# mcu_stm32f4.net
KiCad netlist of a schematic drawn in Altium Designer
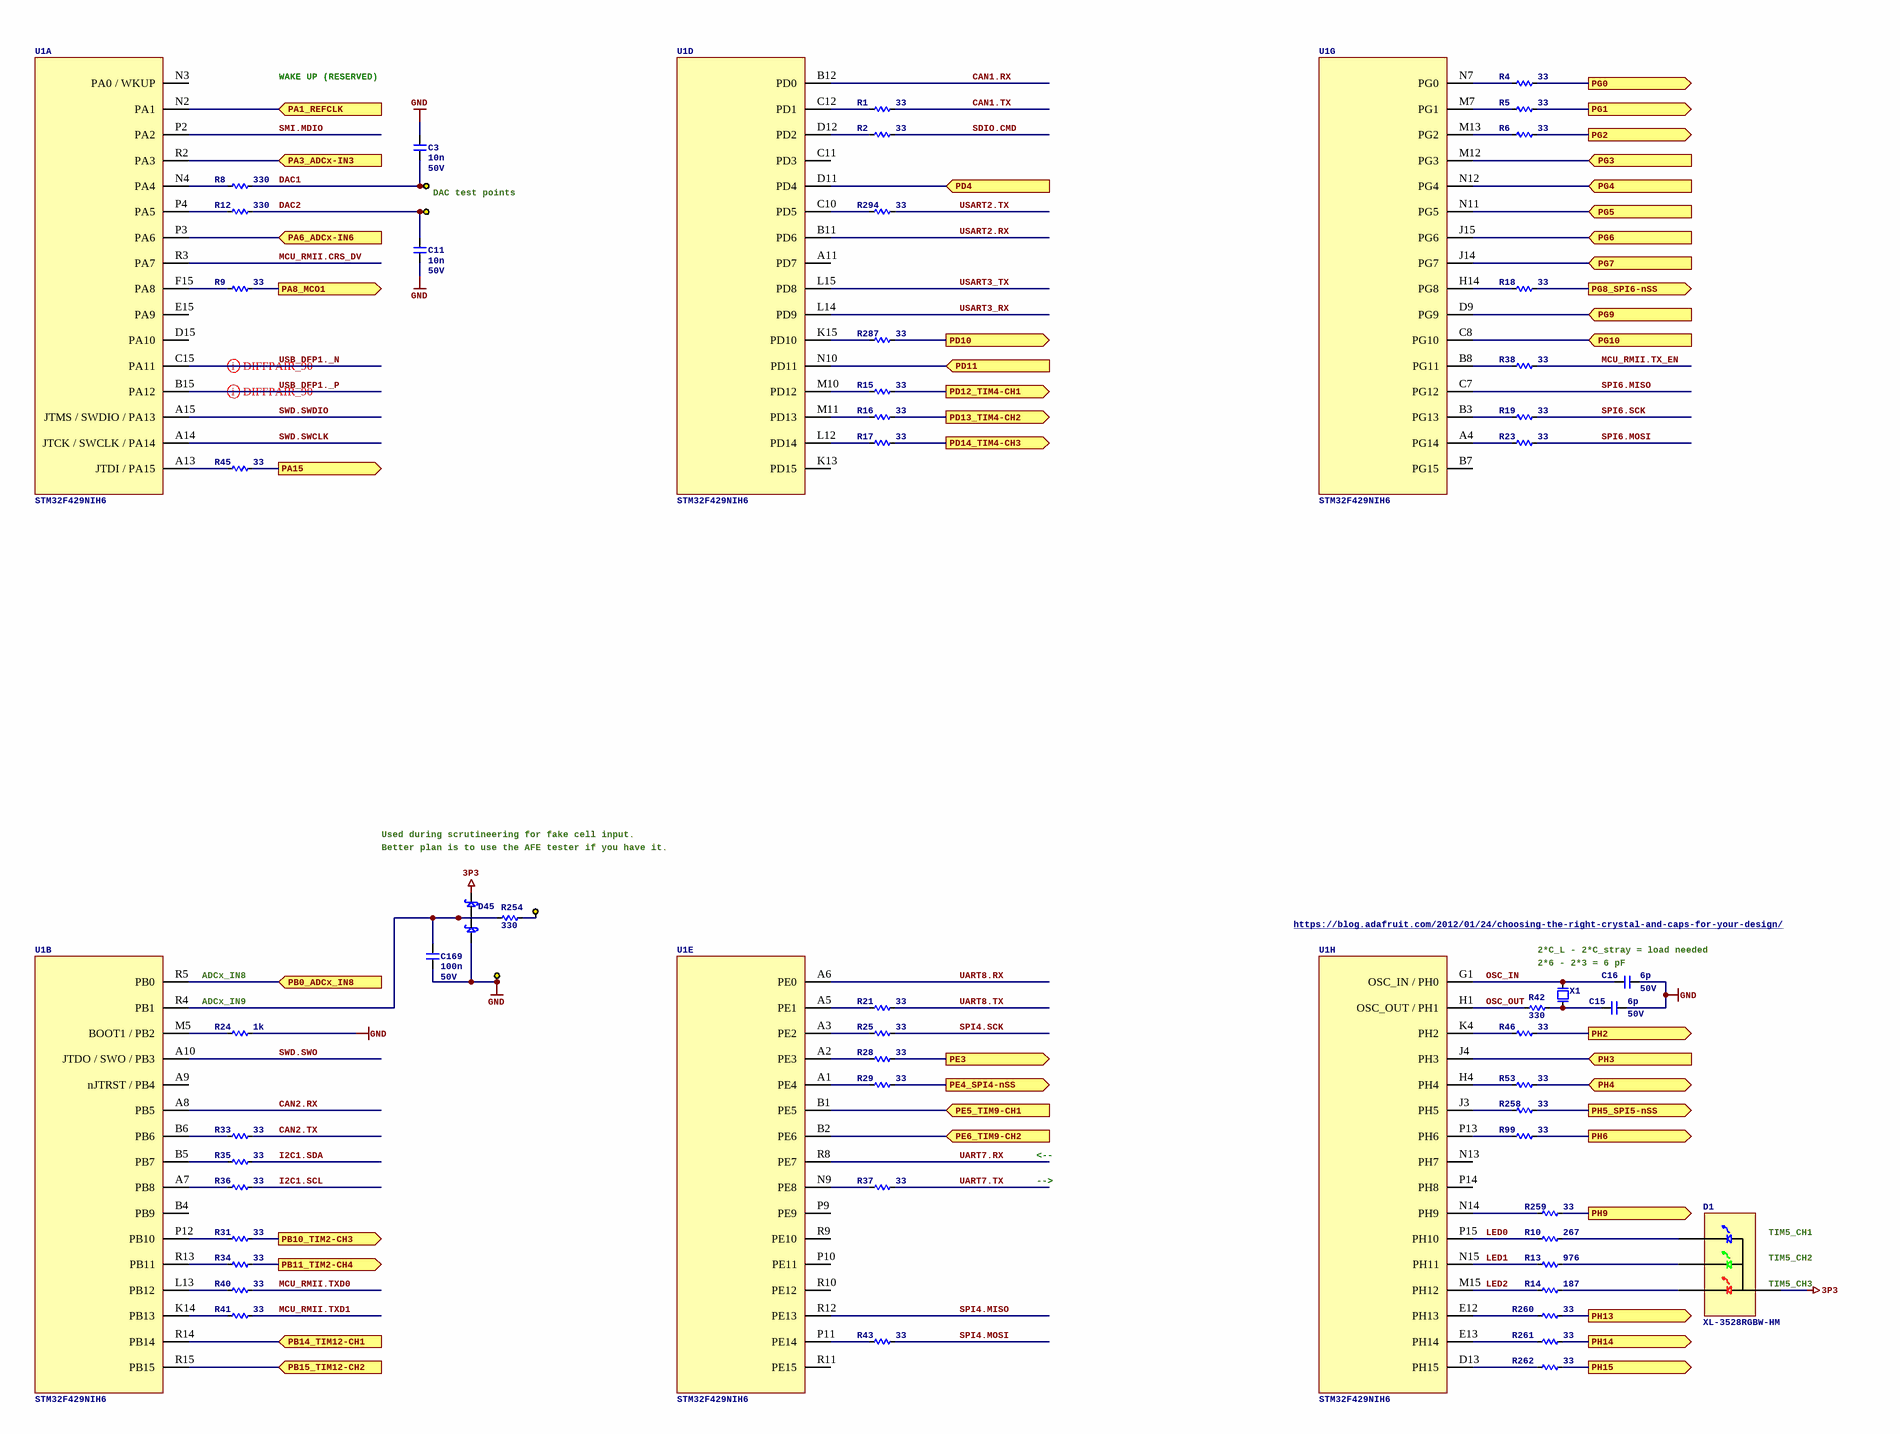
[diagram p0: mcu_stm32f4.SchDoc, top left]
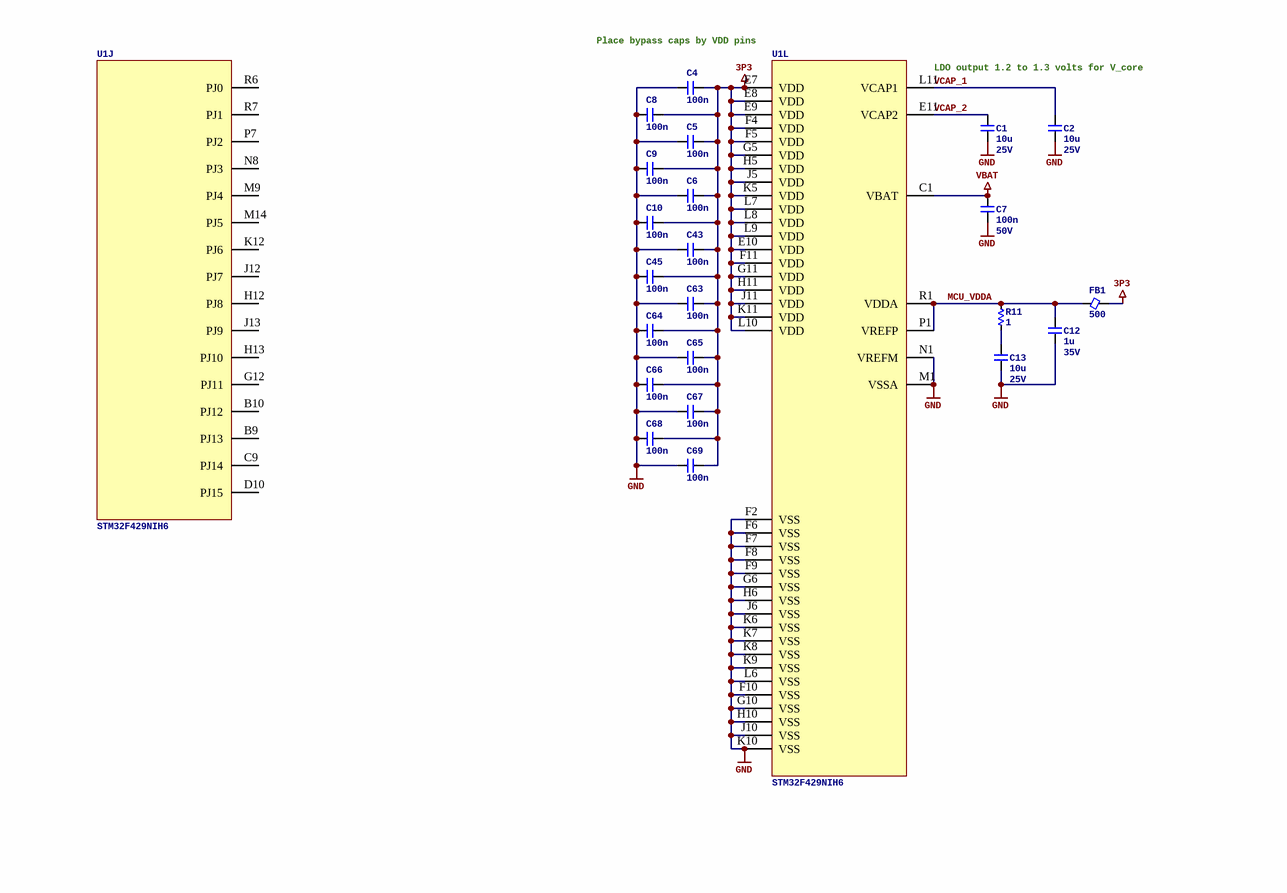
[diagram p1: mcu_stm32f4.SchDoc, top right]
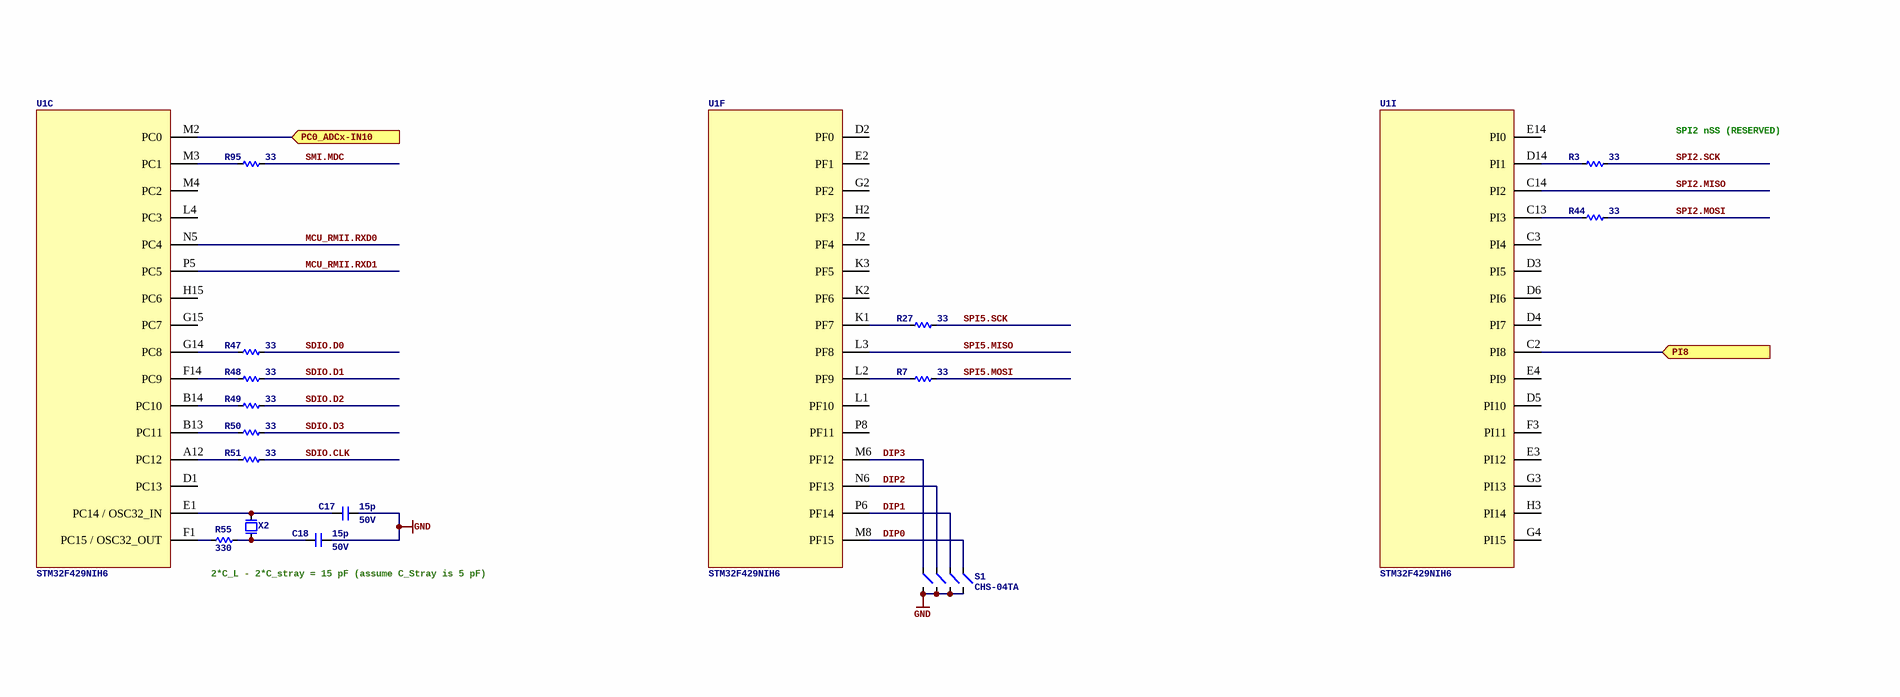
[diagram p2: mcu_stm32f4.SchDoc, bottom left]
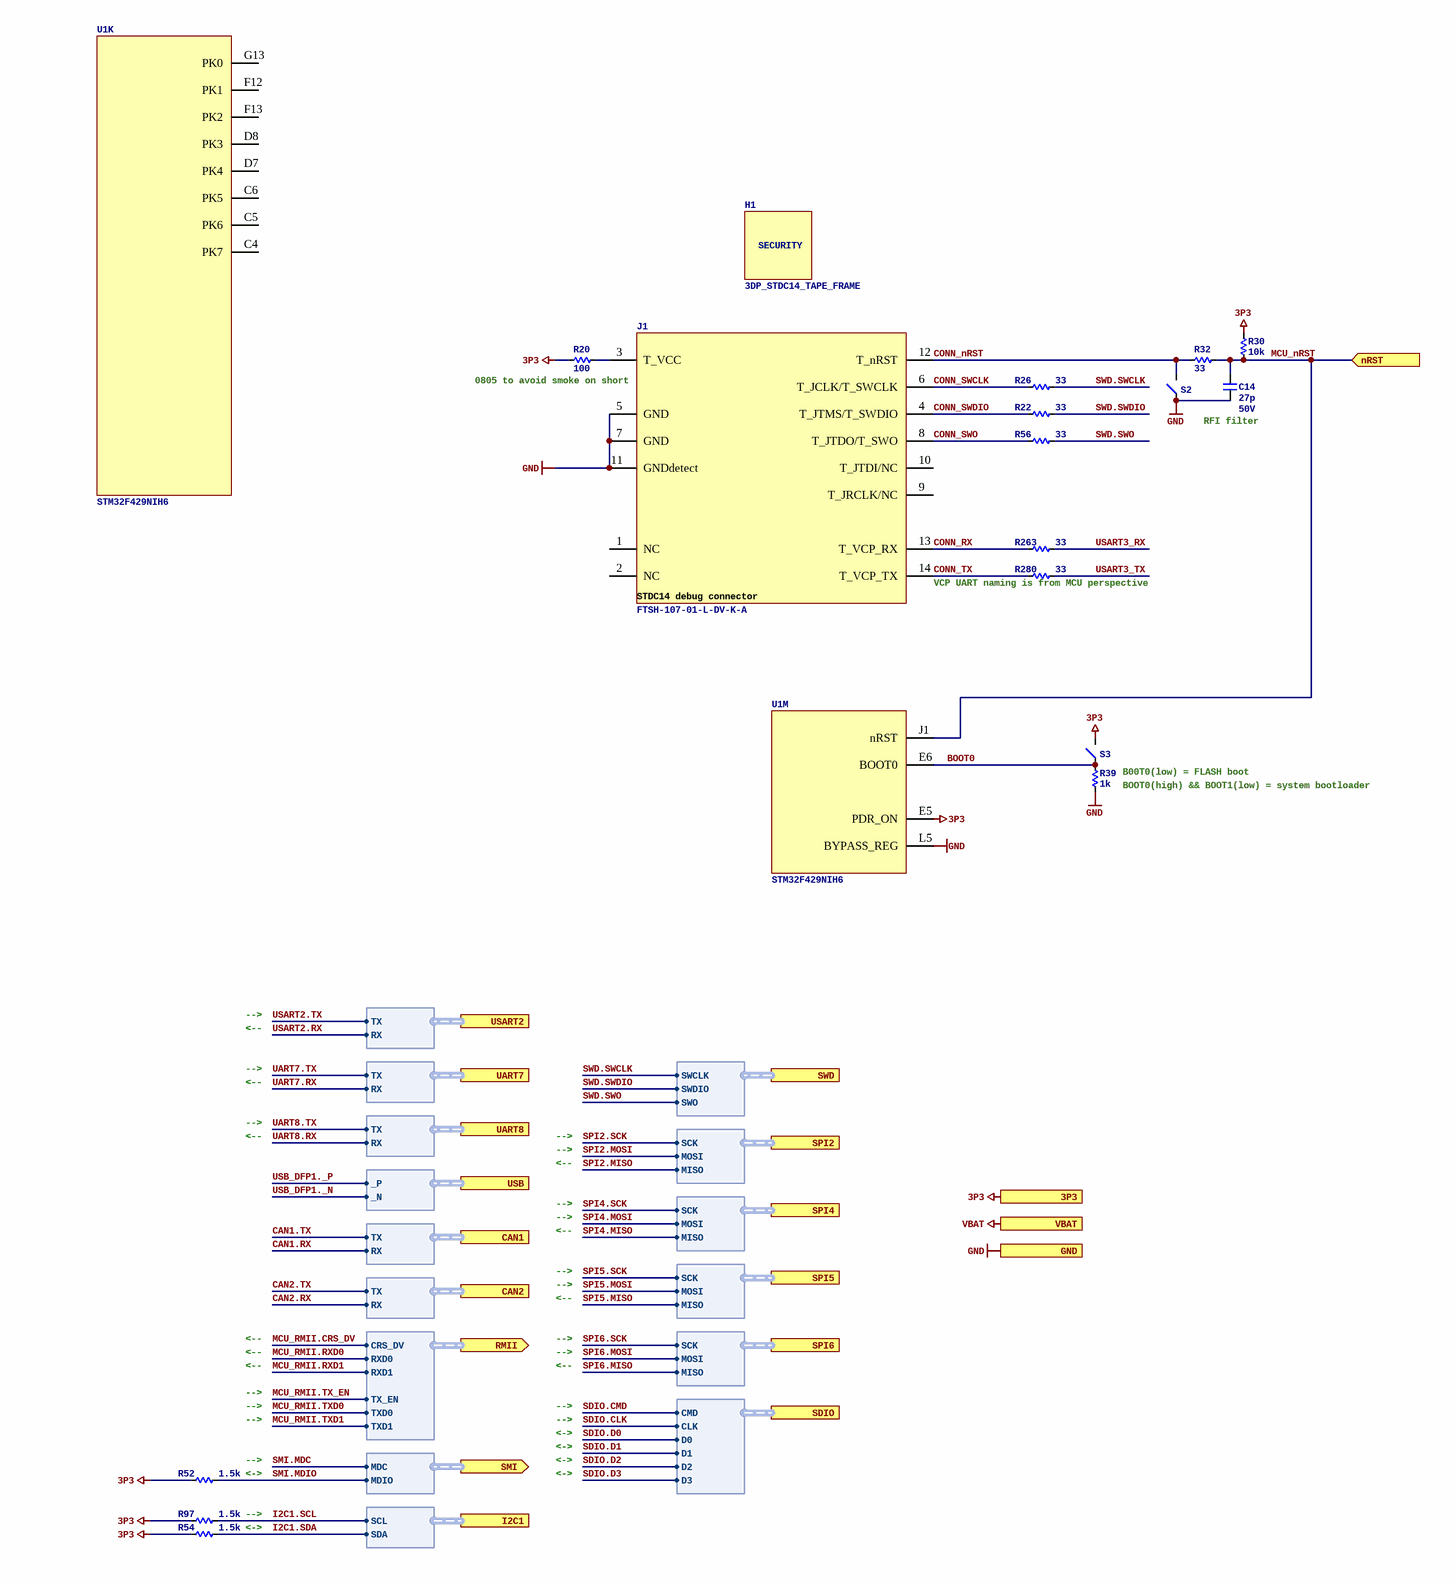
[diagram p3: mcu_stm32f4.SchDoc, bottom right]

(export (version "E")
  (design (tool "Eeschema 10.0.6"))
  (components
    (comp (ref "C1")
      (value "CL10A106MA8NRNC")
      (footprint "C0603")
      (fields
        (field (name "CAPACITANCE") "10u")
        (field (name "MANUFACTURER") "Samsung Electro-Mechanics")
        (field (name "VOLTAGE RATING") "25V")
      )
      (libsource (lib "database") (part "__template_cap"))
    )
    (comp (ref "C2")
      (value "CL10A106MA8NRNC")
      (footprint "C0603")
      (fields
        (field (name "CAPACITANCE") "10u")
        (field (name "MANUFACTURER") "Samsung Electro-Mechanics")
        (field (name "VOLTAGE RATING") "25V")
      )
      (libsource (lib "database") (part "__template_cap"))
    )
    (comp (ref "C3")
      (value "CL05B103KB5NNNC")
      (footprint "C0402")
      (fields
        (field (name "CAPACITANCE") "10n")
        (field (name "MANUFACTURER") "Samsung Electro-Mechanics")
        (field (name "VOLTAGE RATING") "50V")
      )
      (libsource (lib "database") (part "__template_cap"))
    )
    (comp (ref "C4")
      (value "CL05B104KB54PNC")
      (footprint "C0402")
      (fields (field (name "CAPACITANCE") "100n") (field (name "MANUFACTURER") "Samsung Electro-Mechanics"))
      (libsource (lib "database") (part "__template_cap"))
    )
    (comp (ref "C5")
      (value "CL05B104KB54PNC")
      (footprint "C0402")
      (fields (field (name "CAPACITANCE") "100n") (field (name "MANUFACTURER") "Samsung Electro-Mechanics"))
      (libsource (lib "database") (part "__template_cap"))
    )
    (comp (ref "C6")
      (value "CL05B104KB54PNC")
      (footprint "C0402")
      (fields (field (name "CAPACITANCE") "100n") (field (name "MANUFACTURER") "Samsung Electro-Mechanics"))
      (libsource (lib "database") (part "__template_cap"))
    )
    (comp (ref "C7")
      (value "CL05B104KB54PNC")
      (footprint "C0402")
      (fields
        (field (name "CAPACITANCE") "100n")
        (field (name "MANUFACTURER") "Samsung Electro-Mechanics")
        (field (name "VOLTAGE RATING") "50V")
      )
      (libsource (lib "database") (part "__template_cap"))
    )
    (comp (ref "C8")
      (value "CL05B104KB54PNC")
      (footprint "C0402")
      (fields (field (name "CAPACITANCE") "100n") (field (name "MANUFACTURER") "Samsung Electro-Mechanics"))
      (libsource (lib "database") (part "__template_cap"))
    )
    (comp (ref "C9")
      (value "CL05B104KB54PNC")
      (footprint "C0402")
      (fields (field (name "CAPACITANCE") "100n") (field (name "MANUFACTURER") "Samsung Electro-Mechanics"))
      (libsource (lib "database") (part "__template_cap"))
    )
    (comp (ref "C10")
      (value "CL05B104KB54PNC")
      (footprint "C0402")
      (fields (field (name "CAPACITANCE") "100n") (field (name "MANUFACTURER") "Samsung Electro-Mechanics"))
      (libsource (lib "database") (part "__template_cap"))
    )
    (comp (ref "C11")
      (value "CL05B103KB5NNNC")
      (footprint "C0402")
      (fields
        (field (name "CAPACITANCE") "10n")
        (field (name "MANUFACTURER") "Samsung Electro-Mechanics")
        (field (name "VOLTAGE RATING") "50V")
      )
      (libsource (lib "database") (part "__template_cap"))
    )
    (comp (ref "C12")
      (value "GMK107AB7105KAHT")
      (footprint "C0603")
      (fields
        (field (name "CAPACITANCE") "1u")
        (field (name "MANUFACTURER") "Taiyo Yuden")
        (field (name "VOLTAGE RATING") "35V")
      )
      (libsource (lib "database") (part "__template_cap"))
    )
    (comp (ref "C13")
      (value "CL21B106KAYQNNE")
      (footprint "C0805")
      (fields
        (field (name "CAPACITANCE") "10u")
        (field (name "MANUFACTURER") "Samsung Electro-Mechanics")
        (field (name "VOLTAGE RATING") "25V")
      )
      (libsource (lib "database") (part "__template_cap"))
    )
    (comp (ref "C14")
      (value "0402CG270J500NT")
      (footprint "C0402")
      (fields
        (field (name "CAPACITANCE") "27p")
        (field (name "MANUFACTURER") "FH(Guangdong Fenghua Advanced Tech)")
        (field (name "VOLTAGE RATING") "50V")
      )
      (libsource (lib "database") (part "__template_cap"))
    )
    (comp (ref "C15")
      (value "0402CG6R0C500NT")
      (footprint "C0402")
      (fields
        (field (name "CAPACITANCE") "6p")
        (field (name "MANUFACTURER") "FH(Guangdong Fenghua Advanced Tech)")
        (field (name "VOLTAGE RATING") "50V")
      )
      (libsource (lib "database") (part "__template_cap"))
    )
    (comp (ref "C16")
      (value "0402CG6R0C500NT")
      (footprint "C0402")
      (fields
        (field (name "CAPACITANCE") "6p")
        (field (name "MANUFACTURER") "FH(Guangdong Fenghua Advanced Tech)")
        (field (name "VOLTAGE RATING") "50V")
      )
      (libsource (lib "database") (part "__template_cap"))
    )
    (comp (ref "C17")
      (value "0402CG150J500NT")
      (footprint "C0402")
      (fields
        (field (name "CAPACITANCE") "15p")
        (field (name "MANUFACTURER") "FH(Guangdong Fenghua Advanced Tech)")
        (field (name "VOLTAGE RATING") "50V")
      )
      (libsource (lib "database") (part "__template_cap"))
    )
    (comp (ref "C18")
      (value "0402CG150J500NT")
      (footprint "C0402")
      (fields
        (field (name "CAPACITANCE") "15p")
        (field (name "MANUFACTURER") "FH(Guangdong Fenghua Advanced Tech)")
        (field (name "VOLTAGE RATING") "50V")
      )
      (libsource (lib "database") (part "__template_cap"))
    )
    (comp (ref "C43")
      (value "CL05B104KB54PNC")
      (footprint "C0402")
      (fields (field (name "CAPACITANCE") "100n") (field (name "MANUFACTURER") "Samsung Electro-Mechanics"))
      (libsource (lib "database") (part "__template_cap"))
    )
    (comp (ref "C45")
      (value "CL05B104KB54PNC")
      (footprint "C0402")
      (fields (field (name "CAPACITANCE") "100n") (field (name "MANUFACTURER") "Samsung Electro-Mechanics"))
      (libsource (lib "database") (part "__template_cap"))
    )
    (comp (ref "C63")
      (value "CL05B104KB54PNC")
      (footprint "C0402")
      (fields (field (name "CAPACITANCE") "100n") (field (name "MANUFACTURER") "Samsung Electro-Mechanics"))
      (libsource (lib "database") (part "__template_cap"))
    )
    (comp (ref "C64")
      (value "CL05B104KB54PNC")
      (footprint "C0402")
      (fields (field (name "CAPACITANCE") "100n") (field (name "MANUFACTURER") "Samsung Electro-Mechanics"))
      (libsource (lib "database") (part "__template_cap"))
    )
    (comp (ref "C65")
      (value "CL05B104KB54PNC")
      (footprint "C0402")
      (fields (field (name "CAPACITANCE") "100n") (field (name "MANUFACTURER") "Samsung Electro-Mechanics"))
      (libsource (lib "database") (part "__template_cap"))
    )
    (comp (ref "C66")
      (value "CL05B104KB54PNC")
      (footprint "C0402")
      (fields (field (name "CAPACITANCE") "100n") (field (name "MANUFACTURER") "Samsung Electro-Mechanics"))
      (libsource (lib "database") (part "__template_cap"))
    )
    (comp (ref "C67")
      (value "CL05B104KB54PNC")
      (footprint "C0402")
      (fields (field (name "CAPACITANCE") "100n") (field (name "MANUFACTURER") "Samsung Electro-Mechanics"))
      (libsource (lib "database") (part "__template_cap"))
    )
    (comp (ref "C68")
      (value "CL05B104KB54PNC")
      (footprint "C0402")
      (fields (field (name "CAPACITANCE") "100n") (field (name "MANUFACTURER") "Samsung Electro-Mechanics"))
      (libsource (lib "database") (part "__template_cap"))
    )
    (comp (ref "C69")
      (value "CL05B104KB54PNC")
      (footprint "C0402")
      (fields (field (name "CAPACITANCE") "100n") (field (name "MANUFACTURER") "Samsung Electro-Mechanics"))
      (libsource (lib "database") (part "__template_cap"))
    )
    (comp (ref "C169")
      (value "CL05B104KB54PNC")
      (footprint "C0402")
      (fields
        (field (name "CAPACITANCE") "100n")
        (field (name "MANUFACTURER") "Samsung Electro-Mechanics")
        (field (name "VOLTAGE RATING") "50V")
      )
      (libsource (lib "database") (part "__template_cap"))
    )
    (comp (ref "D1")
      (value "XL-3528RGBW-HM")
      (footprint "LED_RGB_SMD3528-4P")
      (description "LED Multi-Color Chip Red/Green/Blue 621nm/525nm/468nm 25mA/15mA/15mA 4-Pin PLCC T/R")
      (fields (field (name "MANUFACTURER") "XINGLIGHT"))
      (libsource (lib "SSCP") (part "LED_RGB_XL-3528RGBW-HM"))
    )
    (comp (ref "D45")
      (value "BAT54SLT1G")
      (footprint "3SOT23")
      (description "DIODE SCHOTTKY DUAL 30V SOT23")
      (fields (field (name "MANUFACTURER") "ON Semiconductor"))
      (libsource (lib "SSCP") (part "SCHOTTKY_30V_DUAL_BAT54SLT1G"))
    )
    (comp (ref "FB1")
      (value "BLM15AX601SN1D")
      (footprint "FB0402")
      (fields (field (name "MANUFACTURER") "Murata Electronics") (field (name "CURRENT RATING (MA)") "500"))
      (libsource (lib "database") (part "__template_fb"))
    )
    (comp (ref "H1")
      (value "3DP_STDC14_TAPE_FRAME")
      (footprint "3DP_STDC14_TAPE_FRAME")
      (description "3D-printed plastic frame used for security tape around STDC14 programming header")
      (fields (field (name "MANUFACTURER") "SSCP"))
      (libsource (lib "SSCP") (part "3DP_STDC14_TAPE_FRAME"))
    )
    (comp (ref "J1")
      (value "FTSH-107-01-L-DV-K-A")
      (footprint "SAMTEC_FTSH-107-01-L-DV-K-A")
      (description "Connector Header Surface Mount 14 position 0.050\" (1.27mm)")
      (fields (field (name "MANUFACTURER") "Samtec"))
      (libsource (lib "SSCP") (part "CONN_14POS_50MIL_ST_CORTEX_DEBUG_VCP"))
    )
    (comp (ref "R1")
      (value "33")
      (footprint "R0402")
      (fields
        (field (name "TOLERANCE") "1%")
        (field (name "MANUFACTURER PART NUMBER") "0402WGF330JTCE")
        (field (name "MANUFACTURER") "UNI-ROYAL(Uniroyal Elec)")
      )
      (libsource (lib "database") (part "__template_resistor"))
    )
    (comp (ref "R2")
      (value "33")
      (footprint "R0402")
      (fields
        (field (name "TOLERANCE") "1%")
        (field (name "MANUFACTURER PART NUMBER") "0402WGF330JTCE")
        (field (name "MANUFACTURER") "UNI-ROYAL(Uniroyal Elec)")
      )
      (libsource (lib "database") (part "__template_resistor"))
    )
    (comp (ref "R3")
      (value "33")
      (footprint "R0402")
      (fields
        (field (name "TOLERANCE") "1%")
        (field (name "MANUFACTURER PART NUMBER") "0402WGF330JTCE")
        (field (name "MANUFACTURER") "UNI-ROYAL(Uniroyal Elec)")
      )
      (libsource (lib "database") (part "__template_resistor"))
    )
    (comp (ref "R4")
      (value "33")
      (footprint "R0402")
      (fields
        (field (name "TOLERANCE") "1%")
        (field (name "MANUFACTURER PART NUMBER") "0402WGF330JTCE")
        (field (name "MANUFACTURER") "UNI-ROYAL(Uniroyal Elec)")
      )
      (libsource (lib "database") (part "__template_resistor"))
    )
    (comp (ref "R5")
      (value "33")
      (footprint "R0402")
      (fields
        (field (name "TOLERANCE") "1%")
        (field (name "MANUFACTURER PART NUMBER") "0402WGF330JTCE")
        (field (name "MANUFACTURER") "UNI-ROYAL(Uniroyal Elec)")
      )
      (libsource (lib "database") (part "__template_resistor"))
    )
    (comp (ref "R6")
      (value "33")
      (footprint "R0402")
      (fields
        (field (name "TOLERANCE") "1%")
        (field (name "MANUFACTURER PART NUMBER") "0402WGF330JTCE")
        (field (name "MANUFACTURER") "UNI-ROYAL(Uniroyal Elec)")
      )
      (libsource (lib "database") (part "__template_resistor"))
    )
    (comp (ref "R7")
      (value "33")
      (footprint "R0402")
      (fields
        (field (name "TOLERANCE") "1%")
        (field (name "MANUFACTURER PART NUMBER") "0402WGF330JTCE")
        (field (name "MANUFACTURER") "UNI-ROYAL(Uniroyal Elec)")
      )
      (libsource (lib "database") (part "__template_resistor"))
    )
    (comp (ref "R8")
      (value "330")
      (footprint "R0402")
      (fields
        (field (name "TOLERANCE") "1%")
        (field (name "MANUFACTURER PART NUMBER") "0402WGF3300TCE")
        (field (name "MANUFACTURER") "UNI-ROYAL(Uniroyal Elec)")
      )
      (libsource (lib "database") (part "__template_resistor"))
    )
    (comp (ref "R9")
      (value "33")
      (footprint "R0402")
      (fields
        (field (name "TOLERANCE") "1%")
        (field (name "MANUFACTURER PART NUMBER") "0402WGF330JTCE")
        (field (name "MANUFACTURER") "UNI-ROYAL(Uniroyal Elec)")
      )
      (libsource (lib "database") (part "__template_resistor"))
    )
    (comp (ref "R10")
      (value "267")
      (footprint "R0402")
      (fields
        (field (name "TOLERANCE") "1%")
        (field (name "MANUFACTURER PART NUMBER") "FRC0402F2670TS")
        (field (name "MANUFACTURER") "FOJAN")
      )
      (libsource (lib "database") (part "__template_resistor"))
    )
    (comp (ref "R11")
      (value "1")
      (footprint "R0402")
      (fields
        (field (name "TOLERANCE") "1%")
        (field (name "MANUFACTURER PART NUMBER") "CRCW04021R00FKED")
        (field (name "MANUFACTURER") "Vishay Intertech")
      )
      (libsource (lib "database") (part "__template_resistor"))
    )
    (comp (ref "R12")
      (value "330")
      (footprint "R0402")
      (fields
        (field (name "TOLERANCE") "1%")
        (field (name "MANUFACTURER PART NUMBER") "0402WGF3300TCE")
        (field (name "MANUFACTURER") "UNI-ROYAL(Uniroyal Elec)")
      )
      (libsource (lib "database") (part "__template_resistor"))
    )
    (comp (ref "R13")
      (value "976")
      (footprint "R0402")
      (fields
        (field (name "TOLERANCE") "1%")
        (field (name "MANUFACTURER PART NUMBER") "RTT029760FTH")
        (field (name "MANUFACTURER") "RALEC")
      )
      (libsource (lib "database") (part "__template_resistor"))
    )
    (comp (ref "R14")
      (value "187")
      (footprint "R0402")
      (fields
        (field (name "TOLERANCE") "1%")
        (field (name "MANUFACTURER PART NUMBER") "ERJ2RKF1870X")
        (field (name "MANUFACTURER") "PANASONIC")
      )
      (libsource (lib "database") (part "__template_resistor"))
    )
    (comp (ref "R15")
      (value "33")
      (footprint "R0402")
      (fields
        (field (name "TOLERANCE") "1%")
        (field (name "MANUFACTURER PART NUMBER") "0402WGF330JTCE")
        (field (name "MANUFACTURER") "UNI-ROYAL(Uniroyal Elec)")
      )
      (libsource (lib "database") (part "__template_resistor"))
    )
    (comp (ref "R16")
      (value "33")
      (footprint "R0402")
      (fields
        (field (name "TOLERANCE") "1%")
        (field (name "MANUFACTURER PART NUMBER") "0402WGF330JTCE")
        (field (name "MANUFACTURER") "UNI-ROYAL(Uniroyal Elec)")
      )
      (libsource (lib "database") (part "__template_resistor"))
    )
    (comp (ref "R17")
      (value "33")
      (footprint "R0402")
      (fields
        (field (name "TOLERANCE") "1%")
        (field (name "MANUFACTURER PART NUMBER") "0402WGF330JTCE")
        (field (name "MANUFACTURER") "UNI-ROYAL(Uniroyal Elec)")
      )
      (libsource (lib "database") (part "__template_resistor"))
    )
    (comp (ref "R18")
      (value "33")
      (footprint "R0402")
      (fields
        (field (name "TOLERANCE") "1%")
        (field (name "MANUFACTURER PART NUMBER") "0402WGF330JTCE")
        (field (name "MANUFACTURER") "UNI-ROYAL(Uniroyal Elec)")
      )
      (libsource (lib "database") (part "__template_resistor"))
    )
    (comp (ref "R19")
      (value "33")
      (footprint "R0402")
      (fields
        (field (name "TOLERANCE") "1%")
        (field (name "MANUFACTURER PART NUMBER") "0402WGF330JTCE")
        (field (name "MANUFACTURER") "UNI-ROYAL(Uniroyal Elec)")
      )
      (libsource (lib "database") (part "__template_resistor"))
    )
    (comp (ref "R20")
      (value "100")
      (footprint "R0805")
      (fields
        (field (name "TOLERANCE") "1%")
        (field (name "MANUFACTURER PART NUMBER") "ERJP06F1000V")
        (field (name "MANUFACTURER") "PANASONIC")
      )
      (libsource (lib "database") (part "__template_resistor"))
    )
    (comp (ref "R21")
      (value "33")
      (footprint "R0402")
      (fields
        (field (name "TOLERANCE") "1%")
        (field (name "MANUFACTURER PART NUMBER") "0402WGF330JTCE")
        (field (name "MANUFACTURER") "UNI-ROYAL(Uniroyal Elec)")
      )
      (libsource (lib "database") (part "__template_resistor"))
    )
    (comp (ref "R22")
      (value "33")
      (footprint "R0402")
      (fields
        (field (name "TOLERANCE") "1%")
        (field (name "MANUFACTURER PART NUMBER") "0402WGF330JTCE")
        (field (name "MANUFACTURER") "UNI-ROYAL(Uniroyal Elec)")
      )
      (libsource (lib "database") (part "__template_resistor"))
    )
    (comp (ref "R23")
      (value "33")
      (footprint "R0402")
      (fields
        (field (name "TOLERANCE") "1%")
        (field (name "MANUFACTURER PART NUMBER") "0402WGF330JTCE")
        (field (name "MANUFACTURER") "UNI-ROYAL(Uniroyal Elec)")
      )
      (libsource (lib "database") (part "__template_resistor"))
    )
    (comp (ref "R24")
      (value "1k")
      (footprint "R0402")
      (fields
        (field (name "TOLERANCE") "1%")
        (field (name "MANUFACTURER PART NUMBER") "0402WGF1001TCE")
        (field (name "MANUFACTURER") "UNI-ROYAL(Uniroyal Elec)")
      )
      (libsource (lib "database") (part "__template_resistor"))
    )
    (comp (ref "R25")
      (value "33")
      (footprint "R0402")
      (fields
        (field (name "TOLERANCE") "1%")
        (field (name "MANUFACTURER PART NUMBER") "0402WGF330JTCE")
        (field (name "MANUFACTURER") "UNI-ROYAL(Uniroyal Elec)")
      )
      (libsource (lib "database") (part "__template_resistor"))
    )
    (comp (ref "R26")
      (value "33")
      (footprint "R0402")
      (fields
        (field (name "TOLERANCE") "1%")
        (field (name "MANUFACTURER PART NUMBER") "0402WGF330JTCE")
        (field (name "MANUFACTURER") "UNI-ROYAL(Uniroyal Elec)")
      )
      (libsource (lib "database") (part "__template_resistor"))
    )
    (comp (ref "R27")
      (value "33")
      (footprint "R0402")
      (fields
        (field (name "TOLERANCE") "1%")
        (field (name "MANUFACTURER PART NUMBER") "0402WGF330JTCE")
        (field (name "MANUFACTURER") "UNI-ROYAL(Uniroyal Elec)")
      )
      (libsource (lib "database") (part "__template_resistor"))
    )
    (comp (ref "R28")
      (value "33")
      (footprint "R0402")
      (fields
        (field (name "TOLERANCE") "1%")
        (field (name "MANUFACTURER PART NUMBER") "0402WGF330JTCE")
        (field (name "MANUFACTURER") "UNI-ROYAL(Uniroyal Elec)")
      )
      (libsource (lib "database") (part "__template_resistor"))
    )
    (comp (ref "R29")
      (value "33")
      (footprint "R0402")
      (fields
        (field (name "TOLERANCE") "1%")
        (field (name "MANUFACTURER PART NUMBER") "0402WGF330JTCE")
        (field (name "MANUFACTURER") "UNI-ROYAL(Uniroyal Elec)")
      )
      (libsource (lib "database") (part "__template_resistor"))
    )
    (comp (ref "R30")
      (value "10k")
      (footprint "R0402")
      (fields
        (field (name "TOLERANCE") "1%")
        (field (name "MANUFACTURER PART NUMBER") "0402WGF1002TCE")
        (field (name "MANUFACTURER") "UNI-ROYAL(Uniroyal Elec)")
      )
      (libsource (lib "database") (part "__template_resistor"))
    )
    (comp (ref "R31")
      (value "33")
      (footprint "R0402")
      (fields
        (field (name "TOLERANCE") "1%")
        (field (name "MANUFACTURER PART NUMBER") "0402WGF330JTCE")
        (field (name "MANUFACTURER") "UNI-ROYAL(Uniroyal Elec)")
      )
      (libsource (lib "database") (part "__template_resistor"))
    )
    (comp (ref "R32")
      (value "33")
      (footprint "R0402")
      (fields
        (field (name "TOLERANCE") "1%")
        (field (name "MANUFACTURER PART NUMBER") "0402WGF330JTCE")
        (field (name "MANUFACTURER") "UNI-ROYAL(Uniroyal Elec)")
      )
      (libsource (lib "database") (part "__template_resistor"))
    )
    (comp (ref "R33")
      (value "33")
      (footprint "R0402")
      (fields
        (field (name "TOLERANCE") "1%")
        (field (name "MANUFACTURER PART NUMBER") "0402WGF330JTCE")
        (field (name "MANUFACTURER") "UNI-ROYAL(Uniroyal Elec)")
      )
      (libsource (lib "database") (part "__template_resistor"))
    )
    (comp (ref "R34")
      (value "33")
      (footprint "R0402")
      (fields
        (field (name "TOLERANCE") "1%")
        (field (name "MANUFACTURER PART NUMBER") "0402WGF330JTCE")
        (field (name "MANUFACTURER") "UNI-ROYAL(Uniroyal Elec)")
      )
      (libsource (lib "database") (part "__template_resistor"))
    )
    (comp (ref "R35")
      (value "33")
      (footprint "R0402")
      (fields
        (field (name "TOLERANCE") "1%")
        (field (name "MANUFACTURER PART NUMBER") "0402WGF330JTCE")
        (field (name "MANUFACTURER") "UNI-ROYAL(Uniroyal Elec)")
      )
      (libsource (lib "database") (part "__template_resistor"))
    )
    (comp (ref "R36")
      (value "33")
      (footprint "R0402")
      (fields
        (field (name "TOLERANCE") "1%")
        (field (name "MANUFACTURER PART NUMBER") "0402WGF330JTCE")
        (field (name "MANUFACTURER") "UNI-ROYAL(Uniroyal Elec)")
      )
      (libsource (lib "database") (part "__template_resistor"))
    )
    (comp (ref "R37")
      (value "33")
      (footprint "R0402")
      (fields
        (field (name "TOLERANCE") "1%")
        (field (name "MANUFACTURER PART NUMBER") "0402WGF330JTCE")
        (field (name "MANUFACTURER") "UNI-ROYAL(Uniroyal Elec)")
      )
      (libsource (lib "database") (part "__template_resistor"))
    )
    (comp (ref "R38")
      (value "33")
      (footprint "R0402")
      (fields
        (field (name "TOLERANCE") "1%")
        (field (name "MANUFACTURER PART NUMBER") "0402WGF330JTCE")
        (field (name "MANUFACTURER") "UNI-ROYAL(Uniroyal Elec)")
      )
      (libsource (lib "database") (part "__template_resistor"))
    )
    (comp (ref "R39")
      (value "1k")
      (footprint "R0402")
      (fields
        (field (name "TOLERANCE") "1%")
        (field (name "MANUFACTURER PART NUMBER") "0402WGF1001TCE")
        (field (name "MANUFACTURER") "UNI-ROYAL(Uniroyal Elec)")
      )
      (libsource (lib "database") (part "__template_resistor"))
    )
    (comp (ref "R40")
      (value "33")
      (footprint "R0402")
      (fields
        (field (name "TOLERANCE") "1%")
        (field (name "MANUFACTURER PART NUMBER") "0402WGF330JTCE")
        (field (name "MANUFACTURER") "UNI-ROYAL(Uniroyal Elec)")
      )
      (libsource (lib "database") (part "__template_resistor"))
    )
    (comp (ref "R41")
      (value "33")
      (footprint "R0402")
      (fields
        (field (name "TOLERANCE") "1%")
        (field (name "MANUFACTURER PART NUMBER") "0402WGF330JTCE")
        (field (name "MANUFACTURER") "UNI-ROYAL(Uniroyal Elec)")
      )
      (libsource (lib "database") (part "__template_resistor"))
    )
    (comp (ref "R42")
      (value "330")
      (footprint "R0402")
      (fields
        (field (name "TOLERANCE") "1%")
        (field (name "MANUFACTURER PART NUMBER") "0402WGF3300TCE")
        (field (name "MANUFACTURER") "UNI-ROYAL(Uniroyal Elec)")
      )
      (libsource (lib "database") (part "__template_resistor"))
    )
    (comp (ref "R43")
      (value "33")
      (footprint "R0402")
      (fields
        (field (name "TOLERANCE") "1%")
        (field (name "MANUFACTURER PART NUMBER") "0402WGF330JTCE")
        (field (name "MANUFACTURER") "UNI-ROYAL(Uniroyal Elec)")
      )
      (libsource (lib "database") (part "__template_resistor"))
    )
    (comp (ref "R44")
      (value "33")
      (footprint "R0402")
      (fields
        (field (name "TOLERANCE") "1%")
        (field (name "MANUFACTURER PART NUMBER") "0402WGF330JTCE")
        (field (name "MANUFACTURER") "UNI-ROYAL(Uniroyal Elec)")
      )
      (libsource (lib "database") (part "__template_resistor"))
    )
    (comp (ref "R45")
      (value "33")
      (footprint "R0402")
      (fields
        (field (name "TOLERANCE") "1%")
        (field (name "MANUFACTURER PART NUMBER") "0402WGF330JTCE")
        (field (name "MANUFACTURER") "UNI-ROYAL(Uniroyal Elec)")
      )
      (libsource (lib "database") (part "__template_resistor"))
    )
    (comp (ref "R46")
      (value "33")
      (footprint "R0402")
      (fields
        (field (name "TOLERANCE") "1%")
        (field (name "MANUFACTURER PART NUMBER") "0402WGF330JTCE")
        (field (name "MANUFACTURER") "UNI-ROYAL(Uniroyal Elec)")
      )
      (libsource (lib "database") (part "__template_resistor"))
    )
    (comp (ref "R47")
      (value "33")
      (footprint "R0402")
      (fields
        (field (name "TOLERANCE") "1%")
        (field (name "MANUFACTURER PART NUMBER") "0402WGF330JTCE")
        (field (name "MANUFACTURER") "UNI-ROYAL(Uniroyal Elec)")
      )
      (libsource (lib "database") (part "__template_resistor"))
    )
    (comp (ref "R48")
      (value "33")
      (footprint "R0402")
      (fields
        (field (name "TOLERANCE") "1%")
        (field (name "MANUFACTURER PART NUMBER") "0402WGF330JTCE")
        (field (name "MANUFACTURER") "UNI-ROYAL(Uniroyal Elec)")
      )
      (libsource (lib "database") (part "__template_resistor"))
    )
    (comp (ref "R49")
      (value "33")
      (footprint "R0402")
      (fields
        (field (name "TOLERANCE") "1%")
        (field (name "MANUFACTURER PART NUMBER") "0402WGF330JTCE")
        (field (name "MANUFACTURER") "UNI-ROYAL(Uniroyal Elec)")
      )
      (libsource (lib "database") (part "__template_resistor"))
    )
    (comp (ref "R50")
      (value "33")
      (footprint "R0402")
      (fields
        (field (name "TOLERANCE") "1%")
        (field (name "MANUFACTURER PART NUMBER") "0402WGF330JTCE")
        (field (name "MANUFACTURER") "UNI-ROYAL(Uniroyal Elec)")
      )
      (libsource (lib "database") (part "__template_resistor"))
    )
    (comp (ref "R51")
      (value "33")
      (footprint "R0402")
      (fields
        (field (name "TOLERANCE") "1%")
        (field (name "MANUFACTURER PART NUMBER") "0402WGF330JTCE")
        (field (name "MANUFACTURER") "UNI-ROYAL(Uniroyal Elec)")
      )
      (libsource (lib "database") (part "__template_resistor"))
    )
    (comp (ref "R52")
      (value "1.5k")
      (footprint "R0402")
      (fields
        (field (name "TOLERANCE") "1%")
        (field (name "MANUFACTURER PART NUMBER") "0402WGF1501TCE")
        (field (name "MANUFACTURER") "UNI-ROYAL(Uniroyal Elec)")
      )
      (libsource (lib "database") (part "__template_resistor"))
    )
    (comp (ref "R53")
      (value "33")
      (footprint "R0402")
      (fields
        (field (name "TOLERANCE") "1%")
        (field (name "MANUFACTURER PART NUMBER") "0402WGF330JTCE")
        (field (name "MANUFACTURER") "UNI-ROYAL(Uniroyal Elec)")
      )
      (libsource (lib "database") (part "__template_resistor"))
    )
    (comp (ref "R54")
      (value "1.5k")
      (footprint "R0402")
      (fields
        (field (name "TOLERANCE") "1%")
        (field (name "MANUFACTURER PART NUMBER") "0402WGF1501TCE")
        (field (name "MANUFACTURER") "UNI-ROYAL(Uniroyal Elec)")
      )
      (libsource (lib "database") (part "__template_resistor"))
    )
    (comp (ref "R55")
      (value "330")
      (footprint "R0402")
      (fields
        (field (name "TOLERANCE") "1%")
        (field (name "MANUFACTURER PART NUMBER") "0402WGF3300TCE")
        (field (name "MANUFACTURER") "UNI-ROYAL(Uniroyal Elec)")
      )
      (libsource (lib "database") (part "__template_resistor"))
    )
    (comp (ref "R56")
      (value "33")
      (footprint "R0402")
      (fields
        (field (name "TOLERANCE") "1%")
        (field (name "MANUFACTURER PART NUMBER") "0402WGF330JTCE")
        (field (name "MANUFACTURER") "UNI-ROYAL(Uniroyal Elec)")
      )
      (libsource (lib "database") (part "__template_resistor"))
    )
    (comp (ref "R95")
      (value "33")
      (footprint "R0402")
      (fields
        (field (name "TOLERANCE") "1%")
        (field (name "MANUFACTURER PART NUMBER") "0402WGF330JTCE")
        (field (name "MANUFACTURER") "UNI-ROYAL(Uniroyal Elec)")
      )
      (libsource (lib "database") (part "__template_resistor"))
    )
    (comp (ref "R97")
      (value "1.5k")
      (footprint "R0402")
      (fields
        (field (name "TOLERANCE") "1%")
        (field (name "MANUFACTURER PART NUMBER") "0402WGF1501TCE")
        (field (name "MANUFACTURER") "UNI-ROYAL(Uniroyal Elec)")
      )
      (libsource (lib "database") (part "__template_resistor"))
    )
    (comp (ref "R99")
      (value "33")
      (footprint "R0402")
      (fields
        (field (name "TOLERANCE") "1%")
        (field (name "MANUFACTURER PART NUMBER") "0402WGF330JTCE")
        (field (name "MANUFACTURER") "UNI-ROYAL(Uniroyal Elec)")
      )
      (libsource (lib "database") (part "__template_resistor"))
    )
    (comp (ref "R254")
      (value "330")
      (footprint "R0402")
      (fields
        (field (name "TOLERANCE") "1%")
        (field (name "MANUFACTURER PART NUMBER") "0402WGF3300TCE")
        (field (name "MANUFACTURER") "UNI-ROYAL(Uniroyal Elec)")
      )
      (libsource (lib "database") (part "__template_resistor"))
    )
    (comp (ref "R258")
      (value "33")
      (footprint "R0402")
      (fields
        (field (name "TOLERANCE") "1%")
        (field (name "MANUFACTURER PART NUMBER") "0402WGF330JTCE")
        (field (name "MANUFACTURER") "UNI-ROYAL(Uniroyal Elec)")
      )
      (libsource (lib "database") (part "__template_resistor"))
    )
    (comp (ref "R259")
      (value "33")
      (footprint "R0402")
      (fields
        (field (name "TOLERANCE") "1%")
        (field (name "MANUFACTURER PART NUMBER") "0402WGF330JTCE")
        (field (name "MANUFACTURER") "UNI-ROYAL(Uniroyal Elec)")
      )
      (libsource (lib "database") (part "__template_resistor"))
    )
    (comp (ref "R260")
      (value "33")
      (footprint "R0402")
      (fields
        (field (name "TOLERANCE") "1%")
        (field (name "MANUFACTURER PART NUMBER") "0402WGF330JTCE")
        (field (name "MANUFACTURER") "UNI-ROYAL(Uniroyal Elec)")
      )
      (libsource (lib "database") (part "__template_resistor"))
    )
    (comp (ref "R261")
      (value "33")
      (footprint "R0402")
      (fields
        (field (name "TOLERANCE") "1%")
        (field (name "MANUFACTURER PART NUMBER") "0402WGF330JTCE")
        (field (name "MANUFACTURER") "UNI-ROYAL(Uniroyal Elec)")
      )
      (libsource (lib "database") (part "__template_resistor"))
    )
    (comp (ref "R262")
      (value "33")
      (footprint "R0402")
      (fields
        (field (name "TOLERANCE") "1%")
        (field (name "MANUFACTURER PART NUMBER") "0402WGF330JTCE")
        (field (name "MANUFACTURER") "UNI-ROYAL(Uniroyal Elec)")
      )
      (libsource (lib "database") (part "__template_resistor"))
    )
    (comp (ref "R263")
      (value "33")
      (footprint "R0402")
      (fields
        (field (name "TOLERANCE") "1%")
        (field (name "MANUFACTURER PART NUMBER") "0402WGF330JTCE")
        (field (name "MANUFACTURER") "UNI-ROYAL(Uniroyal Elec)")
      )
      (libsource (lib "database") (part "__template_resistor"))
    )
    (comp (ref "R280")
      (value "33")
      (footprint "R0402")
      (fields
        (field (name "TOLERANCE") "1%")
        (field (name "MANUFACTURER PART NUMBER") "0402WGF330JTCE")
        (field (name "MANUFACTURER") "UNI-ROYAL(Uniroyal Elec)")
      )
      (libsource (lib "database") (part "__template_resistor"))
    )
    (comp (ref "R287")
      (value "33")
      (footprint "R0402")
      (fields
        (field (name "TOLERANCE") "1%")
        (field (name "MANUFACTURER PART NUMBER") "0402WGF330JTCE")
        (field (name "MANUFACTURER") "UNI-ROYAL(Uniroyal Elec)")
      )
      (libsource (lib "database") (part "__template_resistor"))
    )
    (comp (ref "R294")
      (value "33")
      (footprint "R0402")
      (fields
        (field (name "TOLERANCE") "1%")
        (field (name "MANUFACTURER PART NUMBER") "0402WGF330JTCE")
        (field (name "MANUFACTURER") "UNI-ROYAL(Uniroyal Elec)")
      )
      (libsource (lib "database") (part "__template_resistor"))
    )
    (comp (ref "S1")
      (value "CHS-04TA")
      (footprint "SWITCH_NIDEC_CHS-04TA")
      (description "DIP Switch, Slide, SPST, Flush, Recessed, 6VDC, 100mA, CHS Series ¦ Nidec Components CHS-04TA")
      (fields (field (name "MANUFACTURER") "Nidec Copal"))
      (libsource (lib "SSCP") (part "SWITCH_CHS-04TA"))
    )
    (comp (ref "S2")
      (value "TS-1092S-B3D2-G")
      (footprint "SWITCH_TS-1092S-B3D2-G")
      (description "SWITCH TACTILE SPST-NO")
      (fields (field (name "MANUFACTURER") "Yuandi"))
      (libsource (lib "SSCP") (part "SWITCH_TS-1092S-B3D2-G"))
    )
    (comp (ref "S3")
      (value "TS-1092S-B3D2-G")
      (footprint "SWITCH_TS-1092S-B3D2-G")
      (description "SWITCH TACTILE SPST-NO")
      (fields (field (name "MANUFACTURER") "Yuandi"))
      (libsource (lib "SSCP") (part "SWITCH_TS-1092S-B3D2-G"))
    )
    (comp (ref "TP1")
      (value "RH-5002")
      (footprint "TP_RH-5002")
      (fields (field (name "MANUFACTURER") "ronghe"))
      (libsource (lib "database") (part "__template_testpoint"))
    )
    (comp (ref "TP2")
      (value "RH-5002")
      (footprint "TP_RH-5002")
      (fields (field (name "MANUFACTURER") "ronghe"))
      (libsource (lib "database") (part "__template_testpoint"))
    )
    (comp (ref "TP51")
      (value "RH-5000")
      (footprint "TP_RH-5000")
      (fields (field (name "MANUFACTURER") "ronghe"))
      (libsource (lib "database") (part "__template_testpoint"))
    )
    (comp (ref "TP52")
      (value "RH-5001")
      (footprint "TP_RH-5001")
      (fields (field (name "MANUFACTURER") "ronghe"))
      (libsource (lib "database") (part "__template_testpoint"))
    )
    (comp (ref "U1")
      (value "STM32F429NIH6")
      (footprint "ST_TFBGA216")
      (description "ARM® Cortex®-M4 STM32F4 Microcontroller IC 32-Bit 180MHz 2MB (2M x 8) FLASH 216-TFBGA (13x13)")
      (fields (field (name "MANUFACTURER") "STMicroelectronics"))
      (libsource (lib "SSCP") (part "MCU_STM32F429NIH6"))
    )
    (comp (ref "X1")
      (value "XTAL_XRCGB25M000F3A00R0")
      (footprint "4_SMD_2.0X1.6MM")
      (description "CRYSTAL 25.000MHZ 6PF SMD")
      (fields
        (field (name "MANUFACTURER") "Murata")
        (field (name "MANUFACTURER PART NUMBER") "XRCGB25M000F3A00R0")
      )
      (libsource (lib "SSCP") (part "XTAL_XRCGB25M000F3A00R0"))
    )
    (comp (ref "X2")
      (value "XTAL_9HT10-32.768KEZF-T")
      (footprint "XTAL_TXC_9HT10")
      (description "CRYSTAL 32.768 KHZ 12.5 PF SMD")
      (fields
        (field (name "MANUFACTURER") "TXC CORPORATION")
        (field (name "MANUFACTURER PART NUMBER") "9HT10-32.768KEZF-T")
      )
      (libsource (lib "SSCP") (part "XTAL_9HT10-32.768KEZF-T"))
    )
  )
  (nets
    (net (code "10") (name "/BOOT0") (class "Default")
      (node (ref "R39") (pin "1") (pintype "passive"))
      (node (ref "S3") (pin "1") (pintype "passive"))
      (node (ref "U1") (pin "E6") (pinfunction "BOOT0_E6") (pintype "passive"))
    )
    (net (code "11") (name "/CAN1.RX") (class "Default")
      (node (ref "U1") (pin "B12") (pinfunction "PD0_B12") (pintype "passive"))
    )
    (net (code "12") (name "/CAN1.TX") (class "Default") (node (ref "R1") (pin "1") (pintype "passive")))
    (net (code "13") (name "/CAN2.RX") (class "Default")
      (node (ref "U1") (pin "A8") (pinfunction "PB5_A8") (pintype "passive"))
    )
    (net (code "14") (name "/CAN2.TX") (class "Default") (node (ref "R33") (pin "1") (pintype "passive")))
    (net (code "15") (name "/CONN_RX") (class "Default")
      (node (ref "J1") (pin "13") (pinfunction "T_VCP_RX_13") (pintype "passive"))
      (node (ref "R263") (pin "2") (pintype "passive"))
    )
    (net (code "16") (name "/CONN_SWCLK") (class "Default")
      (node (ref "J1") (pin "6") (pinfunction "T_JCLK/T_SWCLK_6") (pintype "passive"))
      (node (ref "R26") (pin "2") (pintype "passive"))
    )
    (net (code "17") (name "/CONN_SWDIO") (class "Default")
      (node (ref "J1") (pin "4") (pinfunction "T_JTMS/T_SWDIO_4") (pintype "passive"))
      (node (ref "R22") (pin "2") (pintype "passive"))
    )
    (net (code "18") (name "/CONN_SWO") (class "Default")
      (node (ref "J1") (pin "8") (pinfunction "T_JTDO/T_SWO_8") (pintype "passive"))
      (node (ref "R56") (pin "2") (pintype "passive"))
    )
    (net (code "19") (name "/CONN_TX") (class "Default")
      (node (ref "J1") (pin "14") (pinfunction "T_VCP_TX_14") (pintype "passive"))
      (node (ref "R280") (pin "2") (pintype "passive"))
    )
    (net (code "20") (name "/CONN_nRST") (class "Default")
      (node (ref "J1") (pin "12") (pinfunction "T_nRST_12") (pintype "passive"))
      (node (ref "R32") (pin "2") (pintype "passive"))
      (node (ref "S2") (pin "2") (pintype "passive"))
    )
    (net (code "21") (name "/DAC1") (class "Default")
      (node (ref "C3") (pin "1") (pintype "passive"))
      (node (ref "R8") (pin "2") (pintype "passive"))
      (node (ref "TP1") (pin "1") (pintype "passive"))
    )
    (net (code "22") (name "/DAC2") (class "Default")
      (node (ref "C11") (pin "1") (pintype "passive"))
      (node (ref "R12") (pin "2") (pintype "passive"))
      (node (ref "TP2") (pin "1") (pintype "passive"))
    )
    (net (code "23") (name "/DIP0") (class "Default")
      (node (ref "S1") (pin "1") (pintype "passive"))
      (node (ref "U1") (pin "M8") (pinfunction "PF15_M8") (pintype "passive"))
    )
    (net (code "24") (name "/DIP1") (class "Default")
      (node (ref "S1") (pin "3") (pintype "passive"))
      (node (ref "U1") (pin "P6") (pinfunction "PF14_P6") (pintype "passive"))
    )
    (net (code "25") (name "/DIP2") (class "Default")
      (node (ref "S1") (pin "5") (pintype "passive"))
      (node (ref "U1") (pin "N6") (pinfunction "PF13_N6") (pintype "passive"))
    )
    (net (code "26") (name "/DIP3") (class "Default")
      (node (ref "S1") (pin "7") (pintype "passive"))
      (node (ref "U1") (pin "M6") (pinfunction "PF12_M6") (pintype "passive"))
    )
    (net (code "27") (name "/I2C1.SCL") (class "Default")
      (node (ref "R36") (pin "1") (pintype "passive"))
      (node (ref "R97") (pin "1") (pintype "passive"))
    )
    (net (code "28") (name "/I2C1.SDA") (class "Default")
      (node (ref "R35") (pin "1") (pintype "passive"))
      (node (ref "R54") (pin "1") (pintype "passive"))
    )
    (net (code "29") (name "/LED0") (class "Default")
      (node (ref "R10") (pin "2") (pintype "passive"))
      (node (ref "U1") (pin "P15") (pinfunction "PH10_P15") (pintype "passive"))
    )
    (net (code "30") (name "/LED1") (class "Default")
      (node (ref "R13") (pin "2") (pintype "passive"))
      (node (ref "U1") (pin "N15") (pinfunction "PH11_N15") (pintype "passive"))
    )
    (net (code "31") (name "/LED2") (class "Default")
      (node (ref "R14") (pin "2") (pintype "passive"))
      (node (ref "U1") (pin "M15") (pinfunction "PH12_M15") (pintype "passive"))
    )
    (net (code "32") (name "/MCU_RMII.CRS_DV") (class "Default")
      (node (ref "U1") (pin "R3") (pinfunction "PA7_R3") (pintype "passive"))
    )
    (net (code "33") (name "/MCU_RMII.RXD0") (class "Default")
      (node (ref "U1") (pin "N5") (pinfunction "PC4_N5") (pintype "passive"))
    )
    (net (code "34") (name "/MCU_RMII.RXD1") (class "Default")
      (node (ref "U1") (pin "P5") (pinfunction "PC5_P5") (pintype "passive"))
    )
    (net (code "35") (name "/MCU_RMII.TXD0") (class "Default")
      (node (ref "R40") (pin "1") (pintype "passive"))
    )
    (net (code "36") (name "/MCU_RMII.TXD1") (class "Default")
      (node (ref "R41") (pin "1") (pintype "passive"))
    )
    (net (code "37") (name "/MCU_RMII.TX_EN") (class "Default")
      (node (ref "R38") (pin "1") (pintype "passive"))
    )
    (net (code "38") (name "/MCU_VDDA") (class "Default")
      (node (ref "C12") (pin "1") (pintype "passive"))
      (node (ref "FB1") (pin "1") (pintype "passive"))
      (node (ref "R11") (pin "2") (pintype "passive"))
      (node (ref "U1") (pin "P1") (pinfunction "VREFP_P1") (pintype "passive"))
      (node (ref "U1") (pin "R1") (pinfunction "VDDA_R1") (pintype "passive"))
    )
    (net (code "39") (name "/MCU_nRST") (class "Default")
      (node (ref "C14") (pin "1") (pintype "passive"))
      (node (ref "R30") (pin "2") (pintype "passive"))
      (node (ref "R32") (pin "1") (pintype "passive"))
      (node (ref "U1") (pin "J1") (pinfunction "nRST_J1") (pintype "passive"))
    )
    (net (code "40") (name "/OSC_IN") (class "Default")
      (node (ref "C16") (pin "1") (pintype "passive"))
      (node (ref "U1") (pin "G1") (pinfunction "OSC_IN_/_PH0_G1") (pintype "passive"))
      (node (ref "X1") (pin "3") (pinfunction "3_3") (pintype "passive"))
    )
    (net (code "41") (name "/OSC_OUT") (class "Default")
      (node (ref "R42") (pin "1") (pintype "passive"))
      (node (ref "U1") (pin "H1") (pinfunction "OSC_OUT_/_PH1_H1") (pintype "passive"))
    )
    (net (code "42") (name "/PA1_REFCLK") (class "Default")
      (node (ref "U1") (pin "N2") (pinfunction "PA1_N2") (pintype "passive"))
    )
    (net (code "43") (name "/PA3_ADCx-IN3") (class "Default")
      (node (ref "U1") (pin "R2") (pinfunction "PA3_R2") (pintype "passive"))
    )
    (net (code "44") (name "/PA6_ADCx-IN6") (class "Default")
      (node (ref "U1") (pin "P3") (pinfunction "PA6_P3") (pintype "passive"))
    )
    (net (code "45") (name "/PA8_MCO1") (class "Default") (node (ref "R9") (pin "1") (pintype "passive")))
    (net (code "46") (name "/PA15") (class "Default") (node (ref "R45") (pin "1") (pintype "passive")))
    (net (code "47") (name "/PB0_ADCx_IN8") (class "Default")
      (node (ref "U1") (pin "R5") (pinfunction "PB0_R5") (pintype "passive"))
    )
    (net (code "48") (name "/PB10_TIM2-CH3") (class "Default")
      (node (ref "R31") (pin "1") (pintype "passive"))
    )
    (net (code "49") (name "/PB11_TIM2-CH4") (class "Default")
      (node (ref "R34") (pin "1") (pintype "passive"))
    )
    (net (code "50") (name "/PB14_TIM12-CH1") (class "Default")
      (node (ref "U1") (pin "R14") (pinfunction "PB14_R14") (pintype "passive"))
    )
    (net (code "51") (name "/PB15_TIM12-CH2") (class "Default")
      (node (ref "U1") (pin "R15") (pinfunction "PB15_R15") (pintype "passive"))
    )
    (net (code "52") (name "/PC0_ADCx-IN10") (class "Default")
      (node (ref "U1") (pin "M2") (pinfunction "PC0_M2") (pintype "passive"))
    )
    (net (code "53") (name "/PD4") (class "Default")
      (node (ref "U1") (pin "D11") (pinfunction "PD4_D11") (pintype "passive"))
    )
    (net (code "54") (name "/PD10") (class "Default") (node (ref "R287") (pin "1") (pintype "passive")))
    (net (code "55") (name "/PD11") (class "Default")
      (node (ref "U1") (pin "N10") (pinfunction "PD11_N10") (pintype "passive"))
    )
    (net (code "56") (name "/PD12_TIM4-CH1") (class "Default")
      (node (ref "R15") (pin "1") (pintype "passive"))
    )
    (net (code "57") (name "/PD13_TIM4-CH2") (class "Default")
      (node (ref "R16") (pin "1") (pintype "passive"))
    )
    (net (code "58") (name "/PD14_TIM4-CH3") (class "Default")
      (node (ref "R17") (pin "1") (pintype "passive"))
    )
    (net (code "59") (name "/PE3") (class "Default") (node (ref "R28") (pin "1") (pintype "passive")))
    (net (code "60") (name "/PE4_SPI4-nSS") (class "Default")
      (node (ref "R29") (pin "1") (pintype "passive"))
    )
    (net (code "61") (name "/PE5_TIM9-CH1") (class "Default")
      (node (ref "U1") (pin "B1") (pinfunction "PE5_B1") (pintype "passive"))
    )
    (net (code "62") (name "/PE6_TIM9-CH2") (class "Default")
      (node (ref "U1") (pin "B2") (pinfunction "PE6_B2") (pintype "passive"))
    )
    (net (code "63") (name "/PG0") (class "Default") (node (ref "R4") (pin "1") (pintype "passive")))
    (net (code "64") (name "/PG1") (class "Default") (node (ref "R5") (pin "1") (pintype "passive")))
    (net (code "65") (name "/PG2") (class "Default") (node (ref "R6") (pin "1") (pintype "passive")))
    (net (code "66") (name "/PG3") (class "Default")
      (node (ref "U1") (pin "M12") (pinfunction "PG3_M12") (pintype "passive"))
    )
    (net (code "67") (name "/PG4") (class "Default")
      (node (ref "U1") (pin "N12") (pinfunction "PG4_N12") (pintype "passive"))
    )
    (net (code "68") (name "/PG5") (class "Default")
      (node (ref "U1") (pin "N11") (pinfunction "PG5_N11") (pintype "passive"))
    )
    (net (code "69") (name "/PG6") (class "Default")
      (node (ref "U1") (pin "J15") (pinfunction "PG6_J15") (pintype "passive"))
    )
    (net (code "70") (name "/PG7") (class "Default")
      (node (ref "U1") (pin "J14") (pinfunction "PG7_J14") (pintype "passive"))
    )
    (net (code "71") (name "/PG8_SPI6-nSS") (class "Default")
      (node (ref "R18") (pin "1") (pintype "passive"))
    )
    (net (code "72") (name "/PG9") (class "Default")
      (node (ref "U1") (pin "D9") (pinfunction "PG9_D9") (pintype "passive"))
    )
    (net (code "73") (name "/PG10") (class "Default")
      (node (ref "U1") (pin "C8") (pinfunction "PG10_C8") (pintype "passive"))
    )
    (net (code "74") (name "/PH2") (class "Default") (node (ref "R46") (pin "1") (pintype "passive")))
    (net (code "75") (name "/PH3") (class "Default")
      (node (ref "U1") (pin "J4") (pinfunction "PH3_J4") (pintype "passive"))
    )
    (net (code "76") (name "/PH4") (class "Default") (node (ref "R53") (pin "1") (pintype "passive")))
    (net (code "77") (name "/PH5_SPI5-nSS") (class "Default")
      (node (ref "R258") (pin "1") (pintype "passive"))
    )
    (net (code "78") (name "/PH6") (class "Default") (node (ref "R99") (pin "1") (pintype "passive")))
    (net (code "79") (name "/PH9") (class "Default") (node (ref "R259") (pin "1") (pintype "passive")))
    (net (code "80") (name "/PH13") (class "Default") (node (ref "R260") (pin "1") (pintype "passive")))
    (net (code "81") (name "/PH14") (class "Default") (node (ref "R261") (pin "1") (pintype "passive")))
    (net (code "82") (name "/PH15") (class "Default") (node (ref "R262") (pin "1") (pintype "passive")))
    (net (code "83") (name "/PI8") (class "Default")
      (node (ref "U1") (pin "C2") (pinfunction "PI8_C2") (pintype "passive"))
    )
    (net (code "84") (name "/SDIO.CLK") (class "Default") (node (ref "R51") (pin "1") (pintype "passive")))
    (net (code "85") (name "/SDIO.CMD") (class "Default") (node (ref "R2") (pin "1") (pintype "passive")))
    (net (code "86") (name "/SDIO.D0") (class "Default") (node (ref "R47") (pin "1") (pintype "passive")))
    (net (code "87") (name "/SDIO.D1") (class "Default") (node (ref "R48") (pin "1") (pintype "passive")))
    (net (code "88") (name "/SDIO.D2") (class "Default") (node (ref "R49") (pin "1") (pintype "passive")))
    (net (code "89") (name "/SDIO.D3") (class "Default") (node (ref "R50") (pin "1") (pintype "passive")))
    (net (code "90") (name "/SMI.MDC") (class "Default") (node (ref "R95") (pin "1") (pintype "passive")))
    (net (code "91") (name "/SMI.MDIO") (class "Default")
      (node (ref "R52") (pin "1") (pintype "passive"))
      (node (ref "U1") (pin "P2") (pinfunction "PA2_P2") (pintype "passive"))
    )
    (net (code "92") (name "/SPI2.MISO") (class "Default")
      (node (ref "U1") (pin "C14") (pinfunction "PI2_C14") (pintype "passive"))
    )
    (net (code "93") (name "/SPI2.MOSI") (class "Default") (node (ref "R44") (pin "1") (pintype "passive")))
    (net (code "94") (name "/SPI2.SCK") (class "Default") (node (ref "R3") (pin "1") (pintype "passive")))
    (net (code "95") (name "/SPI4.MISO") (class "Default")
      (node (ref "U1") (pin "R12") (pinfunction "PE13_R12") (pintype "passive"))
    )
    (net (code "96") (name "/SPI4.MOSI") (class "Default") (node (ref "R43") (pin "1") (pintype "passive")))
    (net (code "97") (name "/SPI4.SCK") (class "Default") (node (ref "R25") (pin "1") (pintype "passive")))
    (net (code "98") (name "/SPI5.MISO") (class "Default")
      (node (ref "U1") (pin "L3") (pinfunction "PF8_L3") (pintype "passive"))
    )
    (net (code "99") (name "/SPI5.MOSI") (class "Default") (node (ref "R7") (pin "1") (pintype "passive")))
    (net (code "100") (name "/SPI5.SCK") (class "Default") (node (ref "R27") (pin "1") (pintype "passive")))
    (net (code "101") (name "/SPI6.MISO") (class "Default")
      (node (ref "U1") (pin "C7") (pinfunction "PG12_C7") (pintype "passive"))
    )
    (net (code "102") (name "/SPI6.MOSI") (class "Default") (node (ref "R23") (pin "1") (pintype "passive")))
    (net (code "103") (name "/SPI6.SCK") (class "Default") (node (ref "R19") (pin "1") (pintype "passive")))
    (net (code "104") (name "/SWD.SWCLK") (class "Default")
      (node (ref "R26") (pin "1") (pintype "passive"))
      (node (ref "U1") (pin "A14") (pinfunction "JTCK_/_SWCLK_/_PA14_A14") (pintype "passive"))
    )
    (net (code "105") (name "/SWD.SWDIO") (class "Default")
      (node (ref "R22") (pin "1") (pintype "passive"))
      (node (ref "U1") (pin "A15") (pinfunction "JTMS_/_SWDIO_/_PA13_A15") (pintype "passive"))
    )
    (net (code "106") (name "/SWD.SWO") (class "Default")
      (node (ref "R56") (pin "1") (pintype "passive"))
      (node (ref "U1") (pin "A10") (pinfunction "JTDO_/_SWO_/_PB3_A10") (pintype "passive"))
    )
    (net (code "107") (name "/UART7.RX") (class "Default")
      (node (ref "U1") (pin "R8") (pinfunction "PE7_R8") (pintype "passive"))
    )
    (net (code "108") (name "/UART7.TX") (class "Default") (node (ref "R37") (pin "1") (pintype "passive")))
    (net (code "109") (name "/UART8.RX") (class "Default")
      (node (ref "U1") (pin "A6") (pinfunction "PE0_A6") (pintype "passive"))
    )
    (net (code "110") (name "/UART8.TX") (class "Default") (node (ref "R21") (pin "1") (pintype "passive")))
    (net (code "111") (name "/USART2.RX") (class "Default")
      (node (ref "U1") (pin "B11") (pinfunction "PD6_B11") (pintype "passive"))
    )
    (net (code "112") (name "/USART2.TX") (class "Default") (node (ref "R294") (pin "1") (pintype "passive")))
    (net (code "113") (name "/USART3_RX") (class "Default")
      (node (ref "R263") (pin "1") (pintype "passive"))
      (node (ref "U1") (pin "L14") (pinfunction "PD9_L14") (pintype "passive"))
    )
    (net (code "114") (name "/USART3_TX") (class "Default")
      (node (ref "R280") (pin "1") (pintype "passive"))
      (node (ref "U1") (pin "L15") (pinfunction "PD8_L15") (pintype "passive"))
    )
    (net (code "115") (name "/USB_DFP1._N") (class "Default")
      (node (ref "U1") (pin "C15") (pinfunction "PA11_C15") (pintype "passive"))
    )
    (net (code "116") (name "/USB_DFP1._P") (class "Default")
      (node (ref "U1") (pin "B15") (pinfunction "PA12_B15") (pintype "passive"))
    )
    (net (code "117") (name "/VCAP_1") (class "Default")
      (node (ref "C2") (pin "1") (pintype "passive"))
      (node (ref "U1") (pin "L11") (pinfunction "VCAP1_L11") (pintype "passive"))
    )
    (net (code "118") (name "/VCAP_2") (class "Default")
      (node (ref "C1") (pin "1") (pintype "passive"))
      (node (ref "U1") (pin "E11") (pinfunction "VCAP2_E11") (pintype "passive"))
    )
    (net (code "128") (name "3P3") (class "Default")
      (node (ref "C10") (pin "1") (pintype "passive"))
      (node (ref "C4") (pin "1") (pintype "passive"))
      (node (ref "C43") (pin "1") (pintype "passive"))
      (node (ref "C45") (pin "1") (pintype "passive"))
      (node (ref "C5") (pin "1") (pintype "passive"))
      (node (ref "C6") (pin "1") (pintype "passive"))
      (node (ref "C63") (pin "1") (pintype "passive"))
      (node (ref "C64") (pin "1") (pintype "passive"))
      (node (ref "C65") (pin "1") (pintype "passive"))
      (node (ref "C66") (pin "1") (pintype "passive"))
      (node (ref "C67") (pin "1") (pintype "passive"))
      (node (ref "C68") (pin "1") (pintype "passive"))
      (node (ref "C69") (pin "1") (pintype "passive"))
      (node (ref "C8") (pin "1") (pintype "passive"))
      (node (ref "C9") (pin "1") (pintype "passive"))
      (node (ref "D1") (pin "2") (pintype "passive"))
      (node (ref "D45") (pin "2") (pintype "passive"))
      (node (ref "FB1") (pin "2") (pintype "passive"))
      (node (ref "R20") (pin "2") (pintype "passive"))
      (node (ref "R30") (pin "1") (pintype "passive"))
      (node (ref "R52") (pin "2") (pintype "passive"))
      (node (ref "R54") (pin "2") (pintype "passive"))
      (node (ref "R97") (pin "2") (pintype "passive"))
      (node (ref "S3") (pin "2") (pintype "passive"))
      (node (ref "U1") (pin "E10") (pinfunction "VDD_E10") (pintype "passive"))
      (node (ref "U1") (pin "E5") (pinfunction "PDR_ON_E5") (pintype "passive"))
      (node (ref "U1") (pin "E7") (pinfunction "VDD_E7") (pintype "passive"))
      (node (ref "U1") (pin "E8") (pinfunction "VDD_E8") (pintype "passive"))
      (node (ref "U1") (pin "E9") (pinfunction "VDD_E9") (pintype "passive"))
      (node (ref "U1") (pin "F11") (pinfunction "VDD_F11") (pintype "passive"))
      (node (ref "U1") (pin "F4") (pinfunction "VDD_F4") (pintype "passive"))
      (node (ref "U1") (pin "F5") (pinfunction "VDD_F5") (pintype "passive"))
      (node (ref "U1") (pin "G11") (pinfunction "VDD_G11") (pintype "passive"))
      (node (ref "U1") (pin "G5") (pinfunction "VDD_G5") (pintype "passive"))
      (node (ref "U1") (pin "H11") (pinfunction "VDD_H11") (pintype "passive"))
      (node (ref "U1") (pin "H5") (pinfunction "VDD_H5") (pintype "passive"))
      (node (ref "U1") (pin "J11") (pinfunction "VDD_J11") (pintype "passive"))
      (node (ref "U1") (pin "J5") (pinfunction "VDD_J5") (pintype "passive"))
      (node (ref "U1") (pin "K11") (pinfunction "VDD_K11") (pintype "passive"))
      (node (ref "U1") (pin "K5") (pinfunction "VDD_K5") (pintype "passive"))
      (node (ref "U1") (pin "L10") (pinfunction "VDD_L10") (pintype "passive"))
      (node (ref "U1") (pin "L7") (pinfunction "VDD_L7") (pintype "passive"))
      (node (ref "U1") (pin "L8") (pinfunction "VDD_L8") (pintype "passive"))
      (node (ref "U1") (pin "L9") (pinfunction "VDD_L9") (pintype "passive"))
    )
    (net (code "129") (name "GND") (class "Default")
      (node (ref "C1") (pin "2") (pintype "passive"))
      (node (ref "C10") (pin "2") (pintype "passive"))
      (node (ref "C11") (pin "2") (pintype "passive"))
      (node (ref "C12") (pin "2") (pintype "passive"))
      (node (ref "C13") (pin "2") (pintype "passive"))
      (node (ref "C14") (pin "2") (pintype "passive"))
      (node (ref "C15") (pin "2") (pintype "passive"))
      (node (ref "C16") (pin "2") (pintype "passive"))
      (node (ref "C169") (pin "2") (pintype "passive"))
      (node (ref "C17") (pin "2") (pintype "passive"))
      (node (ref "C18") (pin "2") (pintype "passive"))
      (node (ref "C2") (pin "2") (pintype "passive"))
      (node (ref "C3") (pin "2") (pintype "passive"))
      (node (ref "C4") (pin "2") (pintype "passive"))
      (node (ref "C43") (pin "2") (pintype "passive"))
      (node (ref "C45") (pin "2") (pintype "passive"))
      (node (ref "C5") (pin "2") (pintype "passive"))
      (node (ref "C6") (pin "2") (pintype "passive"))
      (node (ref "C63") (pin "2") (pintype "passive"))
      (node (ref "C64") (pin "2") (pintype "passive"))
      (node (ref "C65") (pin "2") (pintype "passive"))
      (node (ref "C66") (pin "2") (pintype "passive"))
      (node (ref "C67") (pin "2") (pintype "passive"))
      (node (ref "C68") (pin "2") (pintype "passive"))
      (node (ref "C69") (pin "2") (pintype "passive"))
      (node (ref "C7") (pin "2") (pintype "passive"))
      (node (ref "C8") (pin "2") (pintype "passive"))
      (node (ref "C9") (pin "2") (pintype "passive"))
      (node (ref "D45") (pin "1") (pintype "passive"))
      (node (ref "J1") (pin "11") (pinfunction "GNDdetect_11") (pintype "passive"))
      (node (ref "J1") (pin "5") (pinfunction "GND_5") (pintype "passive"))
      (node (ref "J1") (pin "7") (pinfunction "GND_7") (pintype "passive"))
      (node (ref "R24") (pin "1") (pintype "passive"))
      (node (ref "R39") (pin "2") (pintype "passive"))
      (node (ref "S1") (pin "2") (pintype "passive"))
      (node (ref "S1") (pin "4") (pintype "passive"))
      (node (ref "S1") (pin "6") (pintype "passive"))
      (node (ref "S1") (pin "8") (pintype "passive"))
      (node (ref "S2") (pin "1") (pintype "passive"))
      (node (ref "TP52") (pin "1") (pintype "passive"))
      (node (ref "U1") (pin "F10") (pinfunction "VSS_F10") (pintype "passive"))
      (node (ref "U1") (pin "F2") (pinfunction "VSS_F2") (pintype "passive"))
      (node (ref "U1") (pin "F6") (pinfunction "VSS_F6") (pintype "passive"))
      (node (ref "U1") (pin "F7") (pinfunction "VSS_F7") (pintype "passive"))
      (node (ref "U1") (pin "F8") (pinfunction "VSS_F8") (pintype "passive"))
      (node (ref "U1") (pin "F9") (pinfunction "VSS_F9") (pintype "passive"))
      (node (ref "U1") (pin "G10") (pinfunction "VSS_G10") (pintype "passive"))
      (node (ref "U1") (pin "G6") (pinfunction "VSS_G6") (pintype "passive"))
      (node (ref "U1") (pin "H10") (pinfunction "VSS_H10") (pintype "passive"))
      (node (ref "U1") (pin "H6") (pinfunction "VSS_H6") (pintype "passive"))
      (node (ref "U1") (pin "J10") (pinfunction "VSS_J10") (pintype "passive"))
      (node (ref "U1") (pin "J6") (pinfunction "VSS_J6") (pintype "passive"))
      (node (ref "U1") (pin "K10") (pinfunction "VSS_K10") (pintype "passive"))
      (node (ref "U1") (pin "K6") (pinfunction "VSS_K6") (pintype "passive"))
      (node (ref "U1") (pin "K7") (pinfunction "VSS_K7") (pintype "passive"))
      (node (ref "U1") (pin "K8") (pinfunction "VSS_K8") (pintype "passive"))
      (node (ref "U1") (pin "K9") (pinfunction "VSS_K9") (pintype "passive"))
      (node (ref "U1") (pin "L5") (pinfunction "BYPASS_REG_L5") (pintype "passive"))
      (node (ref "U1") (pin "L6") (pinfunction "VSS_L6") (pintype "passive"))
      (node (ref "U1") (pin "M1") (pinfunction "VSSA_M1") (pintype "passive"))
      (node (ref "U1") (pin "N1") (pinfunction "VREFM_N1") (pintype "passive"))
    )
    (net (code "130") (name "Net-(C13-Pad1)") (class "Default")
      (node (ref "C13") (pin "1") (pintype "passive"))
      (node (ref "R11") (pin "1") (pintype "passive"))
    )
    (net (code "131") (name "Net-(C15-Pad1)") (class "Default")
      (node (ref "C15") (pin "1") (pintype "passive"))
      (node (ref "R42") (pin "2") (pintype "passive"))
      (node (ref "X1") (pin "1") (pinfunction "1_1") (pintype "passive"))
    )
    (net (code "132") (name "Net-(C18-Pad1)") (class "Default")
      (node (ref "C18") (pin "1") (pintype "passive"))
      (node (ref "R55") (pin "2") (pintype "passive"))
      (node (ref "X2") (pin "1") (pinfunction "1_1") (pintype "passive"))
    )
    (net (code "133") (name "Net-(D1-Pad1)") (class "Default")
      (node (ref "D1") (pin "1") (pintype "passive"))
      (node (ref "R14") (pin "1") (pintype "passive"))
    )
    (net (code "134") (name "Net-(D1-Pad3)") (class "Default")
      (node (ref "D1") (pin "3") (pintype "passive"))
      (node (ref "R13") (pin "1") (pintype "passive"))
    )
    (net (code "135") (name "Net-(D1-Pad4)") (class "Default")
      (node (ref "D1") (pin "4") (pintype "passive"))
      (node (ref "R10") (pin "1") (pintype "passive"))
    )
    (net (code "136") (name "Net-(J1-T_VCC)") (class "Default")
      (node (ref "J1") (pin "3") (pinfunction "T_VCC_3") (pintype "passive"))
      (node (ref "R20") (pin "1") (pintype "passive"))
    )
    (net (code "137") (name "Net-(R254-Pad2)") (class "Default")
      (node (ref "R254") (pin "2") (pintype "passive"))
      (node (ref "TP51") (pin "1") (pintype "passive"))
    )
    (net (code "138") (name "Net-(U1A-JTDI_{slash}_PA15)") (class "Default")
      (node (ref "R45") (pin "2") (pintype "passive"))
      (node (ref "U1") (pin "A13") (pinfunction "JTDI_/_PA15_A13") (pintype "passive"))
    )
    (net (code "139") (name "Net-(U1A-PA4)") (class "Default")
      (node (ref "R8") (pin "1") (pintype "passive"))
      (node (ref "U1") (pin "N4") (pinfunction "PA4_N4") (pintype "passive"))
    )
    (net (code "140") (name "Net-(U1A-PA5)") (class "Default")
      (node (ref "R12") (pin "1") (pintype "passive"))
      (node (ref "U1") (pin "P4") (pinfunction "PA5_P4") (pintype "passive"))
    )
    (net (code "141") (name "Net-(U1A-PA8)") (class "Default")
      (node (ref "R9") (pin "2") (pintype "passive"))
      (node (ref "U1") (pin "F15") (pinfunction "PA8_F15") (pintype "passive"))
    )
    (net (code "142") (name "Net-(U1B-BOOT1_{slash}_PB2)") (class "Default")
      (node (ref "R24") (pin "2") (pintype "passive"))
      (node (ref "U1") (pin "M5") (pinfunction "BOOT1_/_PB2_M5") (pintype "passive"))
    )
    (net (code "143") (name "Net-(U1B-PB1)") (class "Default")
      (node (ref "C169") (pin "1") (pintype "passive"))
      (node (ref "D45") (pin "3") (pintype "passive"))
      (node (ref "R254") (pin "1") (pintype "passive"))
      (node (ref "U1") (pin "R4") (pinfunction "PB1_R4") (pintype "passive"))
    )
    (net (code "144") (name "Net-(U1B-PB6)") (class "Default")
      (node (ref "R33") (pin "2") (pintype "passive"))
      (node (ref "U1") (pin "B6") (pinfunction "PB6_B6") (pintype "passive"))
    )
    (net (code "145") (name "Net-(U1B-PB7)") (class "Default")
      (node (ref "R35") (pin "2") (pintype "passive"))
      (node (ref "U1") (pin "B5") (pinfunction "PB7_B5") (pintype "passive"))
    )
    (net (code "146") (name "Net-(U1B-PB8)") (class "Default")
      (node (ref "R36") (pin "2") (pintype "passive"))
      (node (ref "U1") (pin "A7") (pinfunction "PB8_A7") (pintype "passive"))
    )
    (net (code "147") (name "Net-(U1B-PB10)") (class "Default")
      (node (ref "R31") (pin "2") (pintype "passive"))
      (node (ref "U1") (pin "P12") (pinfunction "PB10_P12") (pintype "passive"))
    )
    (net (code "148") (name "Net-(U1B-PB11)") (class "Default")
      (node (ref "R34") (pin "2") (pintype "passive"))
      (node (ref "U1") (pin "R13") (pinfunction "PB11_R13") (pintype "passive"))
    )
    (net (code "149") (name "Net-(U1B-PB12)") (class "Default")
      (node (ref "R40") (pin "2") (pintype "passive"))
      (node (ref "U1") (pin "L13") (pinfunction "PB12_L13") (pintype "passive"))
    )
    (net (code "150") (name "Net-(U1B-PB13)") (class "Default")
      (node (ref "R41") (pin "2") (pintype "passive"))
      (node (ref "U1") (pin "K14") (pinfunction "PB13_K14") (pintype "passive"))
    )
    (net (code "151") (name "Net-(U1C-PC1)") (class "Default")
      (node (ref "R95") (pin "2") (pintype "passive"))
      (node (ref "U1") (pin "M3") (pinfunction "PC1_M3") (pintype "passive"))
    )
    (net (code "152") (name "Net-(U1C-PC8)") (class "Default")
      (node (ref "R47") (pin "2") (pintype "passive"))
      (node (ref "U1") (pin "G14") (pinfunction "PC8_G14") (pintype "passive"))
    )
    (net (code "153") (name "Net-(U1C-PC9)") (class "Default")
      (node (ref "R48") (pin "2") (pintype "passive"))
      (node (ref "U1") (pin "F14") (pinfunction "PC9_F14") (pintype "passive"))
    )
    (net (code "154") (name "Net-(U1C-PC10)") (class "Default")
      (node (ref "R49") (pin "2") (pintype "passive"))
      (node (ref "U1") (pin "B14") (pinfunction "PC10_B14") (pintype "passive"))
    )
    (net (code "155") (name "Net-(U1C-PC11)") (class "Default")
      (node (ref "R50") (pin "2") (pintype "passive"))
      (node (ref "U1") (pin "B13") (pinfunction "PC11_B13") (pintype "passive"))
    )
    (net (code "156") (name "Net-(U1C-PC12)") (class "Default")
      (node (ref "R51") (pin "2") (pintype "passive"))
      (node (ref "U1") (pin "A12") (pinfunction "PC12_A12") (pintype "passive"))
    )
    (net (code "157") (name "Net-(U1C-PC14_{slash}_OSC32_IN)") (class "Default")
      (node (ref "C17") (pin "1") (pintype "passive"))
      (node (ref "U1") (pin "E1") (pinfunction "PC14_/_OSC32_IN_E1") (pintype "passive"))
      (node (ref "X2") (pin "2") (pinfunction "2_2") (pintype "passive"))
    )
    (net (code "158") (name "Net-(U1C-PC15_{slash}_OSC32_OUT)") (class "Default")
      (node (ref "R55") (pin "1") (pintype "passive"))
      (node (ref "U1") (pin "F1") (pinfunction "PC15_/_OSC32_OUT_F1") (pintype "passive"))
    )
    (net (code "159") (name "Net-(U1D-PD1)") (class "Default")
      (node (ref "R1") (pin "2") (pintype "passive"))
      (node (ref "U1") (pin "C12") (pinfunction "PD1_C12") (pintype "passive"))
    )
    (net (code "160") (name "Net-(U1D-PD2)") (class "Default")
      (node (ref "R2") (pin "2") (pintype "passive"))
      (node (ref "U1") (pin "D12") (pinfunction "PD2_D12") (pintype "passive"))
    )
    (net (code "161") (name "Net-(U1D-PD5)") (class "Default")
      (node (ref "R294") (pin "2") (pintype "passive"))
      (node (ref "U1") (pin "C10") (pinfunction "PD5_C10") (pintype "passive"))
    )
    (net (code "162") (name "Net-(U1D-PD10)") (class "Default")
      (node (ref "R287") (pin "2") (pintype "passive"))
      (node (ref "U1") (pin "K15") (pinfunction "PD10_K15") (pintype "passive"))
    )
    (net (code "163") (name "Net-(U1D-PD12)") (class "Default")
      (node (ref "R15") (pin "2") (pintype "passive"))
      (node (ref "U1") (pin "M10") (pinfunction "PD12_M10") (pintype "passive"))
    )
    (net (code "164") (name "Net-(U1D-PD13)") (class "Default")
      (node (ref "R16") (pin "2") (pintype "passive"))
      (node (ref "U1") (pin "M11") (pinfunction "PD13_M11") (pintype "passive"))
    )
    (net (code "165") (name "Net-(U1D-PD14)") (class "Default")
      (node (ref "R17") (pin "2") (pintype "passive"))
      (node (ref "U1") (pin "L12") (pinfunction "PD14_L12") (pintype "passive"))
    )
    (net (code "166") (name "Net-(U1E-PE1)") (class "Default")
      (node (ref "R21") (pin "2") (pintype "passive"))
      (node (ref "U1") (pin "A5") (pinfunction "PE1_A5") (pintype "passive"))
    )
    (net (code "167") (name "Net-(U1E-PE2)") (class "Default")
      (node (ref "R25") (pin "2") (pintype "passive"))
      (node (ref "U1") (pin "A3") (pinfunction "PE2_A3") (pintype "passive"))
    )
    (net (code "168") (name "Net-(U1E-PE3)") (class "Default")
      (node (ref "R28") (pin "2") (pintype "passive"))
      (node (ref "U1") (pin "A2") (pinfunction "PE3_A2") (pintype "passive"))
    )
    (net (code "169") (name "Net-(U1E-PE4)") (class "Default")
      (node (ref "R29") (pin "2") (pintype "passive"))
      (node (ref "U1") (pin "A1") (pinfunction "PE4_A1") (pintype "passive"))
    )
    (net (code "170") (name "Net-(U1E-PE8)") (class "Default")
      (node (ref "R37") (pin "2") (pintype "passive"))
      (node (ref "U1") (pin "N9") (pinfunction "PE8_N9") (pintype "passive"))
    )
    (net (code "171") (name "Net-(U1E-PE14)") (class "Default")
      (node (ref "R43") (pin "2") (pintype "passive"))
      (node (ref "U1") (pin "P11") (pinfunction "PE14_P11") (pintype "passive"))
    )
    (net (code "172") (name "Net-(U1F-PF7)") (class "Default")
      (node (ref "R27") (pin "2") (pintype "passive"))
      (node (ref "U1") (pin "K1") (pinfunction "PF7_K1") (pintype "passive"))
    )
    (net (code "173") (name "Net-(U1F-PF9)") (class "Default")
      (node (ref "R7") (pin "2") (pintype "passive"))
      (node (ref "U1") (pin "L2") (pinfunction "PF9_L2") (pintype "passive"))
    )
    (net (code "174") (name "Net-(U1G-PG0)") (class "Default")
      (node (ref "R4") (pin "2") (pintype "passive"))
      (node (ref "U1") (pin "N7") (pinfunction "PG0_N7") (pintype "passive"))
    )
    (net (code "175") (name "Net-(U1G-PG1)") (class "Default")
      (node (ref "R5") (pin "2") (pintype "passive"))
      (node (ref "U1") (pin "M7") (pinfunction "PG1_M7") (pintype "passive"))
    )
    (net (code "176") (name "Net-(U1G-PG2)") (class "Default")
      (node (ref "R6") (pin "2") (pintype "passive"))
      (node (ref "U1") (pin "M13") (pinfunction "PG2_M13") (pintype "passive"))
    )
    (net (code "177") (name "Net-(U1G-PG8)") (class "Default")
      (node (ref "R18") (pin "2") (pintype "passive"))
      (node (ref "U1") (pin "H14") (pinfunction "PG8_H14") (pintype "passive"))
    )
    (net (code "178") (name "Net-(U1G-PG11)") (class "Default")
      (node (ref "R38") (pin "2") (pintype "passive"))
      (node (ref "U1") (pin "B8") (pinfunction "PG11_B8") (pintype "passive"))
    )
    (net (code "179") (name "Net-(U1G-PG13)") (class "Default")
      (node (ref "R19") (pin "2") (pintype "passive"))
      (node (ref "U1") (pin "B3") (pinfunction "PG13_B3") (pintype "passive"))
    )
    (net (code "180") (name "Net-(U1G-PG14)") (class "Default")
      (node (ref "R23") (pin "2") (pintype "passive"))
      (node (ref "U1") (pin "A4") (pinfunction "PG14_A4") (pintype "passive"))
    )
    (net (code "181") (name "Net-(U1H-PH2)") (class "Default")
      (node (ref "R46") (pin "2") (pintype "passive"))
      (node (ref "U1") (pin "K4") (pinfunction "PH2_K4") (pintype "passive"))
    )
    (net (code "182") (name "Net-(U1H-PH4)") (class "Default")
      (node (ref "R53") (pin "2") (pintype "passive"))
      (node (ref "U1") (pin "H4") (pinfunction "PH4_H4") (pintype "passive"))
    )
    (net (code "183") (name "Net-(U1H-PH5)") (class "Default")
      (node (ref "R258") (pin "2") (pintype "passive"))
      (node (ref "U1") (pin "J3") (pinfunction "PH5_J3") (pintype "passive"))
    )
    (net (code "184") (name "Net-(U1H-PH6)") (class "Default")
      (node (ref "R99") (pin "2") (pintype "passive"))
      (node (ref "U1") (pin "P13") (pinfunction "PH6_P13") (pintype "passive"))
    )
    (net (code "185") (name "Net-(U1H-PH9)") (class "Default")
      (node (ref "R259") (pin "2") (pintype "passive"))
      (node (ref "U1") (pin "N14") (pinfunction "PH9_N14") (pintype "passive"))
    )
    (net (code "186") (name "Net-(U1H-PH13)") (class "Default")
      (node (ref "R260") (pin "2") (pintype "passive"))
      (node (ref "U1") (pin "E12") (pinfunction "PH13_E12") (pintype "passive"))
    )
    (net (code "187") (name "Net-(U1H-PH14)") (class "Default")
      (node (ref "R261") (pin "2") (pintype "passive"))
      (node (ref "U1") (pin "E13") (pinfunction "PH14_E13") (pintype "passive"))
    )
    (net (code "188") (name "Net-(U1H-PH15)") (class "Default")
      (node (ref "R262") (pin "2") (pintype "passive"))
      (node (ref "U1") (pin "D13") (pinfunction "PH15_D13") (pintype "passive"))
    )
    (net (code "189") (name "Net-(U1I-PI1)") (class "Default")
      (node (ref "R3") (pin "2") (pintype "passive"))
      (node (ref "U1") (pin "D14") (pinfunction "PI1_D14") (pintype "passive"))
    )
    (net (code "190") (name "Net-(U1I-PI3)") (class "Default")
      (node (ref "R44") (pin "2") (pintype "passive"))
      (node (ref "U1") (pin "C13") (pinfunction "PI3_C13") (pintype "passive"))
    )
    (net (code "191") (name "VBAT") (class "Default")
      (node (ref "C7") (pin "1") (pintype "passive"))
      (node (ref "U1") (pin "C1") (pinfunction "VBAT_C1") (pintype "passive"))
    )
    (net (code "192") (name "unconnected-(J1-NC-Pad1)") (class "Default")
      (node (ref "J1") (pin "1") (pinfunction "NC_1") (pintype "passive"))
    )
    (net (code "193") (name "unconnected-(J1-NC-Pad2)") (class "Default")
      (node (ref "J1") (pin "2") (pinfunction "NC_2") (pintype "passive"))
    )
    (net (code "194") (name "unconnected-(J1-T_JRCLK{slash}NC-Pad9)") (class "Default")
      (node (ref "J1") (pin "9") (pinfunction "T_JRCLK/NC_9") (pintype "passive"))
    )
    (net (code "195") (name "unconnected-(J1-T_JTDI{slash}NC-Pad10)") (class "Default")
      (node (ref "J1") (pin "10") (pinfunction "T_JTDI/NC_10") (pintype "passive"))
    )
    (net (code "196") (name "unconnected-(U1A-PA0_{slash}_WKUP-PadN3)") (class "Default")
      (node (ref "U1") (pin "N3") (pinfunction "PA0_/_WKUP_N3") (pintype "passive"))
    )
    (net (code "197") (name "unconnected-(U1A-PA9-PadE15)") (class "Default")
      (node (ref "U1") (pin "E15") (pinfunction "PA9_E15") (pintype "passive"))
    )
    (net (code "198") (name "unconnected-(U1A-PA10-PadD15)") (class "Default")
      (node (ref "U1") (pin "D15") (pinfunction "PA10_D15") (pintype "passive"))
    )
    (net (code "199") (name "unconnected-(U1B-PB9-PadB4)") (class "Default")
      (node (ref "U1") (pin "B4") (pinfunction "PB9_B4") (pintype "passive"))
    )
    (net (code "200") (name "unconnected-(U1B-nJTRST_{slash}_PB4-PadA9)") (class "Default")
      (node (ref "U1") (pin "A9") (pinfunction "nJTRST_/_PB4_A9") (pintype "passive"))
    )
    (net (code "201") (name "unconnected-(U1C-PC2-PadM4)") (class "Default")
      (node (ref "U1") (pin "M4") (pinfunction "PC2_M4") (pintype "passive"))
    )
    (net (code "202") (name "unconnected-(U1C-PC3-PadL4)") (class "Default")
      (node (ref "U1") (pin "L4") (pinfunction "PC3_L4") (pintype "passive"))
    )
    (net (code "203") (name "unconnected-(U1C-PC6-PadH15)") (class "Default")
      (node (ref "U1") (pin "H15") (pinfunction "PC6_H15") (pintype "passive"))
    )
    (net (code "204") (name "unconnected-(U1C-PC7-PadG15)") (class "Default")
      (node (ref "U1") (pin "G15") (pinfunction "PC7_G15") (pintype "passive"))
    )
    (net (code "205") (name "unconnected-(U1C-PC13-PadD1)") (class "Default")
      (node (ref "U1") (pin "D1") (pinfunction "PC13_D1") (pintype "passive"))
    )
    (net (code "206") (name "unconnected-(U1D-PD3-PadC11)") (class "Default")
      (node (ref "U1") (pin "C11") (pinfunction "PD3_C11") (pintype "passive"))
    )
    (net (code "207") (name "unconnected-(U1D-PD7-PadA11)") (class "Default")
      (node (ref "U1") (pin "A11") (pinfunction "PD7_A11") (pintype "passive"))
    )
    (net (code "208") (name "unconnected-(U1D-PD15-PadK13)") (class "Default")
      (node (ref "U1") (pin "K13") (pinfunction "PD15_K13") (pintype "passive"))
    )
    (net (code "209") (name "unconnected-(U1E-PE9-PadP9)") (class "Default")
      (node (ref "U1") (pin "P9") (pinfunction "PE9_P9") (pintype "passive"))
    )
    (net (code "210") (name "unconnected-(U1E-PE10-PadR9)") (class "Default")
      (node (ref "U1") (pin "R9") (pinfunction "PE10_R9") (pintype "passive"))
    )
    (net (code "211") (name "unconnected-(U1E-PE11-PadP10)") (class "Default")
      (node (ref "U1") (pin "P10") (pinfunction "PE11_P10") (pintype "passive"))
    )
    (net (code "212") (name "unconnected-(U1E-PE12-PadR10)") (class "Default")
      (node (ref "U1") (pin "R10") (pinfunction "PE12_R10") (pintype "passive"))
    )
    (net (code "213") (name "unconnected-(U1E-PE15-PadR11)") (class "Default")
      (node (ref "U1") (pin "R11") (pinfunction "PE15_R11") (pintype "passive"))
    )
    (net (code "214") (name "unconnected-(U1F-PF0-PadD2)") (class "Default")
      (node (ref "U1") (pin "D2") (pinfunction "PF0_D2") (pintype "passive"))
    )
    (net (code "215") (name "unconnected-(U1F-PF1-PadE2)") (class "Default")
      (node (ref "U1") (pin "E2") (pinfunction "PF1_E2") (pintype "passive"))
    )
    (net (code "216") (name "unconnected-(U1F-PF2-PadG2)") (class "Default")
      (node (ref "U1") (pin "G2") (pinfunction "PF2_G2") (pintype "passive"))
    )
    (net (code "217") (name "unconnected-(U1F-PF3-PadH2)") (class "Default")
      (node (ref "U1") (pin "H2") (pinfunction "PF3_H2") (pintype "passive"))
    )
    (net (code "218") (name "unconnected-(U1F-PF4-PadJ2)") (class "Default")
      (node (ref "U1") (pin "J2") (pinfunction "PF4_J2") (pintype "passive"))
    )
    (net (code "219") (name "unconnected-(U1F-PF5-PadK3)") (class "Default")
      (node (ref "U1") (pin "K3") (pinfunction "PF5_K3") (pintype "passive"))
    )
    (net (code "220") (name "unconnected-(U1F-PF6-PadK2)") (class "Default")
      (node (ref "U1") (pin "K2") (pinfunction "PF6_K2") (pintype "passive"))
    )
    (net (code "221") (name "unconnected-(U1F-PF10-PadL1)") (class "Default")
      (node (ref "U1") (pin "L1") (pinfunction "PF10_L1") (pintype "passive"))
    )
    (net (code "222") (name "unconnected-(U1F-PF11-PadP8)") (class "Default")
      (node (ref "U1") (pin "P8") (pinfunction "PF11_P8") (pintype "passive"))
    )
    (net (code "223") (name "unconnected-(U1G-PG15-PadB7)") (class "Default")
      (node (ref "U1") (pin "B7") (pinfunction "PG15_B7") (pintype "passive"))
    )
    (net (code "224") (name "unconnected-(U1H-PH7-PadN13)") (class "Default")
      (node (ref "U1") (pin "N13") (pinfunction "PH7_N13") (pintype "passive"))
    )
    (net (code "225") (name "unconnected-(U1H-PH8-PadP14)") (class "Default")
      (node (ref "U1") (pin "P14") (pinfunction "PH8_P14") (pintype "passive"))
    )
    (net (code "226") (name "unconnected-(U1I-PI0-PadE14)") (class "Default")
      (node (ref "U1") (pin "E14") (pinfunction "PI0_E14") (pintype "passive"))
    )
    (net (code "227") (name "unconnected-(U1I-PI4-PadC3)") (class "Default")
      (node (ref "U1") (pin "C3") (pinfunction "PI4_C3") (pintype "passive"))
    )
    (net (code "228") (name "unconnected-(U1I-PI5-PadD3)") (class "Default")
      (node (ref "U1") (pin "D3") (pinfunction "PI5_D3") (pintype "passive"))
    )
    (net (code "229") (name "unconnected-(U1I-PI6-PadD6)") (class "Default")
      (node (ref "U1") (pin "D6") (pinfunction "PI6_D6") (pintype "passive"))
    )
    (net (code "230") (name "unconnected-(U1I-PI7-PadD4)") (class "Default")
      (node (ref "U1") (pin "D4") (pinfunction "PI7_D4") (pintype "passive"))
    )
    (net (code "231") (name "unconnected-(U1I-PI9-PadE4)") (class "Default")
      (node (ref "U1") (pin "E4") (pinfunction "PI9_E4") (pintype "passive"))
    )
    (net (code "232") (name "unconnected-(U1I-PI10-PadD5)") (class "Default")
      (node (ref "U1") (pin "D5") (pinfunction "PI10_D5") (pintype "passive"))
    )
    (net (code "233") (name "unconnected-(U1I-PI11-PadF3)") (class "Default")
      (node (ref "U1") (pin "F3") (pinfunction "PI11_F3") (pintype "passive"))
    )
    (net (code "234") (name "unconnected-(U1I-PI12-PadE3)") (class "Default")
      (node (ref "U1") (pin "E3") (pinfunction "PI12_E3") (pintype "passive"))
    )
    (net (code "235") (name "unconnected-(U1I-PI13-PadG3)") (class "Default")
      (node (ref "U1") (pin "G3") (pinfunction "PI13_G3") (pintype "passive"))
    )
    (net (code "236") (name "unconnected-(U1I-PI14-PadH3)") (class "Default")
      (node (ref "U1") (pin "H3") (pinfunction "PI14_H3") (pintype "passive"))
    )
    (net (code "237") (name "unconnected-(U1I-PI15-PadG4)") (class "Default")
      (node (ref "U1") (pin "G4") (pinfunction "PI15_G4") (pintype "passive"))
    )
    (net (code "238") (name "unconnected-(U1J-PJ0-PadR6)") (class "Default")
      (node (ref "U1") (pin "R6") (pinfunction "PJ0_R6") (pintype "passive"))
    )
    (net (code "239") (name "unconnected-(U1J-PJ1-PadR7)") (class "Default")
      (node (ref "U1") (pin "R7") (pinfunction "PJ1_R7") (pintype "passive"))
    )
    (net (code "240") (name "unconnected-(U1J-PJ2-PadP7)") (class "Default")
      (node (ref "U1") (pin "P7") (pinfunction "PJ2_P7") (pintype "passive"))
    )
    (net (code "241") (name "unconnected-(U1J-PJ3-PadN8)") (class "Default")
      (node (ref "U1") (pin "N8") (pinfunction "PJ3_N8") (pintype "passive"))
    )
    (net (code "242") (name "unconnected-(U1J-PJ4-PadM9)") (class "Default")
      (node (ref "U1") (pin "M9") (pinfunction "PJ4_M9") (pintype "passive"))
    )
    (net (code "243") (name "unconnected-(U1J-PJ5-PadM14)") (class "Default")
      (node (ref "U1") (pin "M14") (pinfunction "PJ5_M14") (pintype "passive"))
    )
    (net (code "244") (name "unconnected-(U1J-PJ6-PadK12)") (class "Default")
      (node (ref "U1") (pin "K12") (pinfunction "PJ6_K12") (pintype "passive"))
    )
    (net (code "245") (name "unconnected-(U1J-PJ7-PadJ12)") (class "Default")
      (node (ref "U1") (pin "J12") (pinfunction "PJ7_J12") (pintype "passive"))
    )
    (net (code "246") (name "unconnected-(U1J-PJ8-PadH12)") (class "Default")
      (node (ref "U1") (pin "H12") (pinfunction "PJ8_H12") (pintype "passive"))
    )
    (net (code "247") (name "unconnected-(U1J-PJ9-PadJ13)") (class "Default")
      (node (ref "U1") (pin "J13") (pinfunction "PJ9_J13") (pintype "passive"))
    )
    (net (code "248") (name "unconnected-(U1J-PJ10-PadH13)") (class "Default")
      (node (ref "U1") (pin "H13") (pinfunction "PJ10_H13") (pintype "passive"))
    )
    (net (code "249") (name "unconnected-(U1J-PJ11-PadG12)") (class "Default")
      (node (ref "U1") (pin "G12") (pinfunction "PJ11_G12") (pintype "passive"))
    )
    (net (code "250") (name "unconnected-(U1J-PJ12-PadB10)") (class "Default")
      (node (ref "U1") (pin "B10") (pinfunction "PJ12_B10") (pintype "passive"))
    )
    (net (code "251") (name "unconnected-(U1J-PJ13-PadB9)") (class "Default")
      (node (ref "U1") (pin "B9") (pinfunction "PJ13_B9") (pintype "passive"))
    )
    (net (code "252") (name "unconnected-(U1J-PJ14-PadC9)") (class "Default")
      (node (ref "U1") (pin "C9") (pinfunction "PJ14_C9") (pintype "passive"))
    )
    (net (code "253") (name "unconnected-(U1J-PJ15-PadD10)") (class "Default")
      (node (ref "U1") (pin "D10") (pinfunction "PJ15_D10") (pintype "passive"))
    )
    (net (code "254") (name "unconnected-(U1K-PK0-PadG13)") (class "Default")
      (node (ref "U1") (pin "G13") (pinfunction "PK0_G13") (pintype "passive"))
    )
    (net (code "255") (name "unconnected-(U1K-PK1-PadF12)") (class "Default")
      (node (ref "U1") (pin "F12") (pinfunction "PK1_F12") (pintype "passive"))
    )
    (net (code "256") (name "unconnected-(U1K-PK2-PadF13)") (class "Default")
      (node (ref "U1") (pin "F13") (pinfunction "PK2_F13") (pintype "passive"))
    )
    (net (code "257") (name "unconnected-(U1K-PK3-PadD8)") (class "Default")
      (node (ref "U1") (pin "D8") (pinfunction "PK3_D8") (pintype "passive"))
    )
    (net (code "258") (name "unconnected-(U1K-PK4-PadD7)") (class "Default")
      (node (ref "U1") (pin "D7") (pinfunction "PK4_D7") (pintype "passive"))
    )
    (net (code "259") (name "unconnected-(U1K-PK5-PadC6)") (class "Default")
      (node (ref "U1") (pin "C6") (pinfunction "PK5_C6") (pintype "passive"))
    )
    (net (code "260") (name "unconnected-(U1K-PK6-PadC5)") (class "Default")
      (node (ref "U1") (pin "C5") (pinfunction "PK6_C5") (pintype "passive"))
    )
    (net (code "261") (name "unconnected-(U1K-PK7-PadC4)") (class "Default")
      (node (ref "U1") (pin "C4") (pinfunction "PK7_C4") (pintype "passive"))
    )
  )
)
